# prototype_rev2.net
KiCad netlist of a schematic drawn in EAGLE
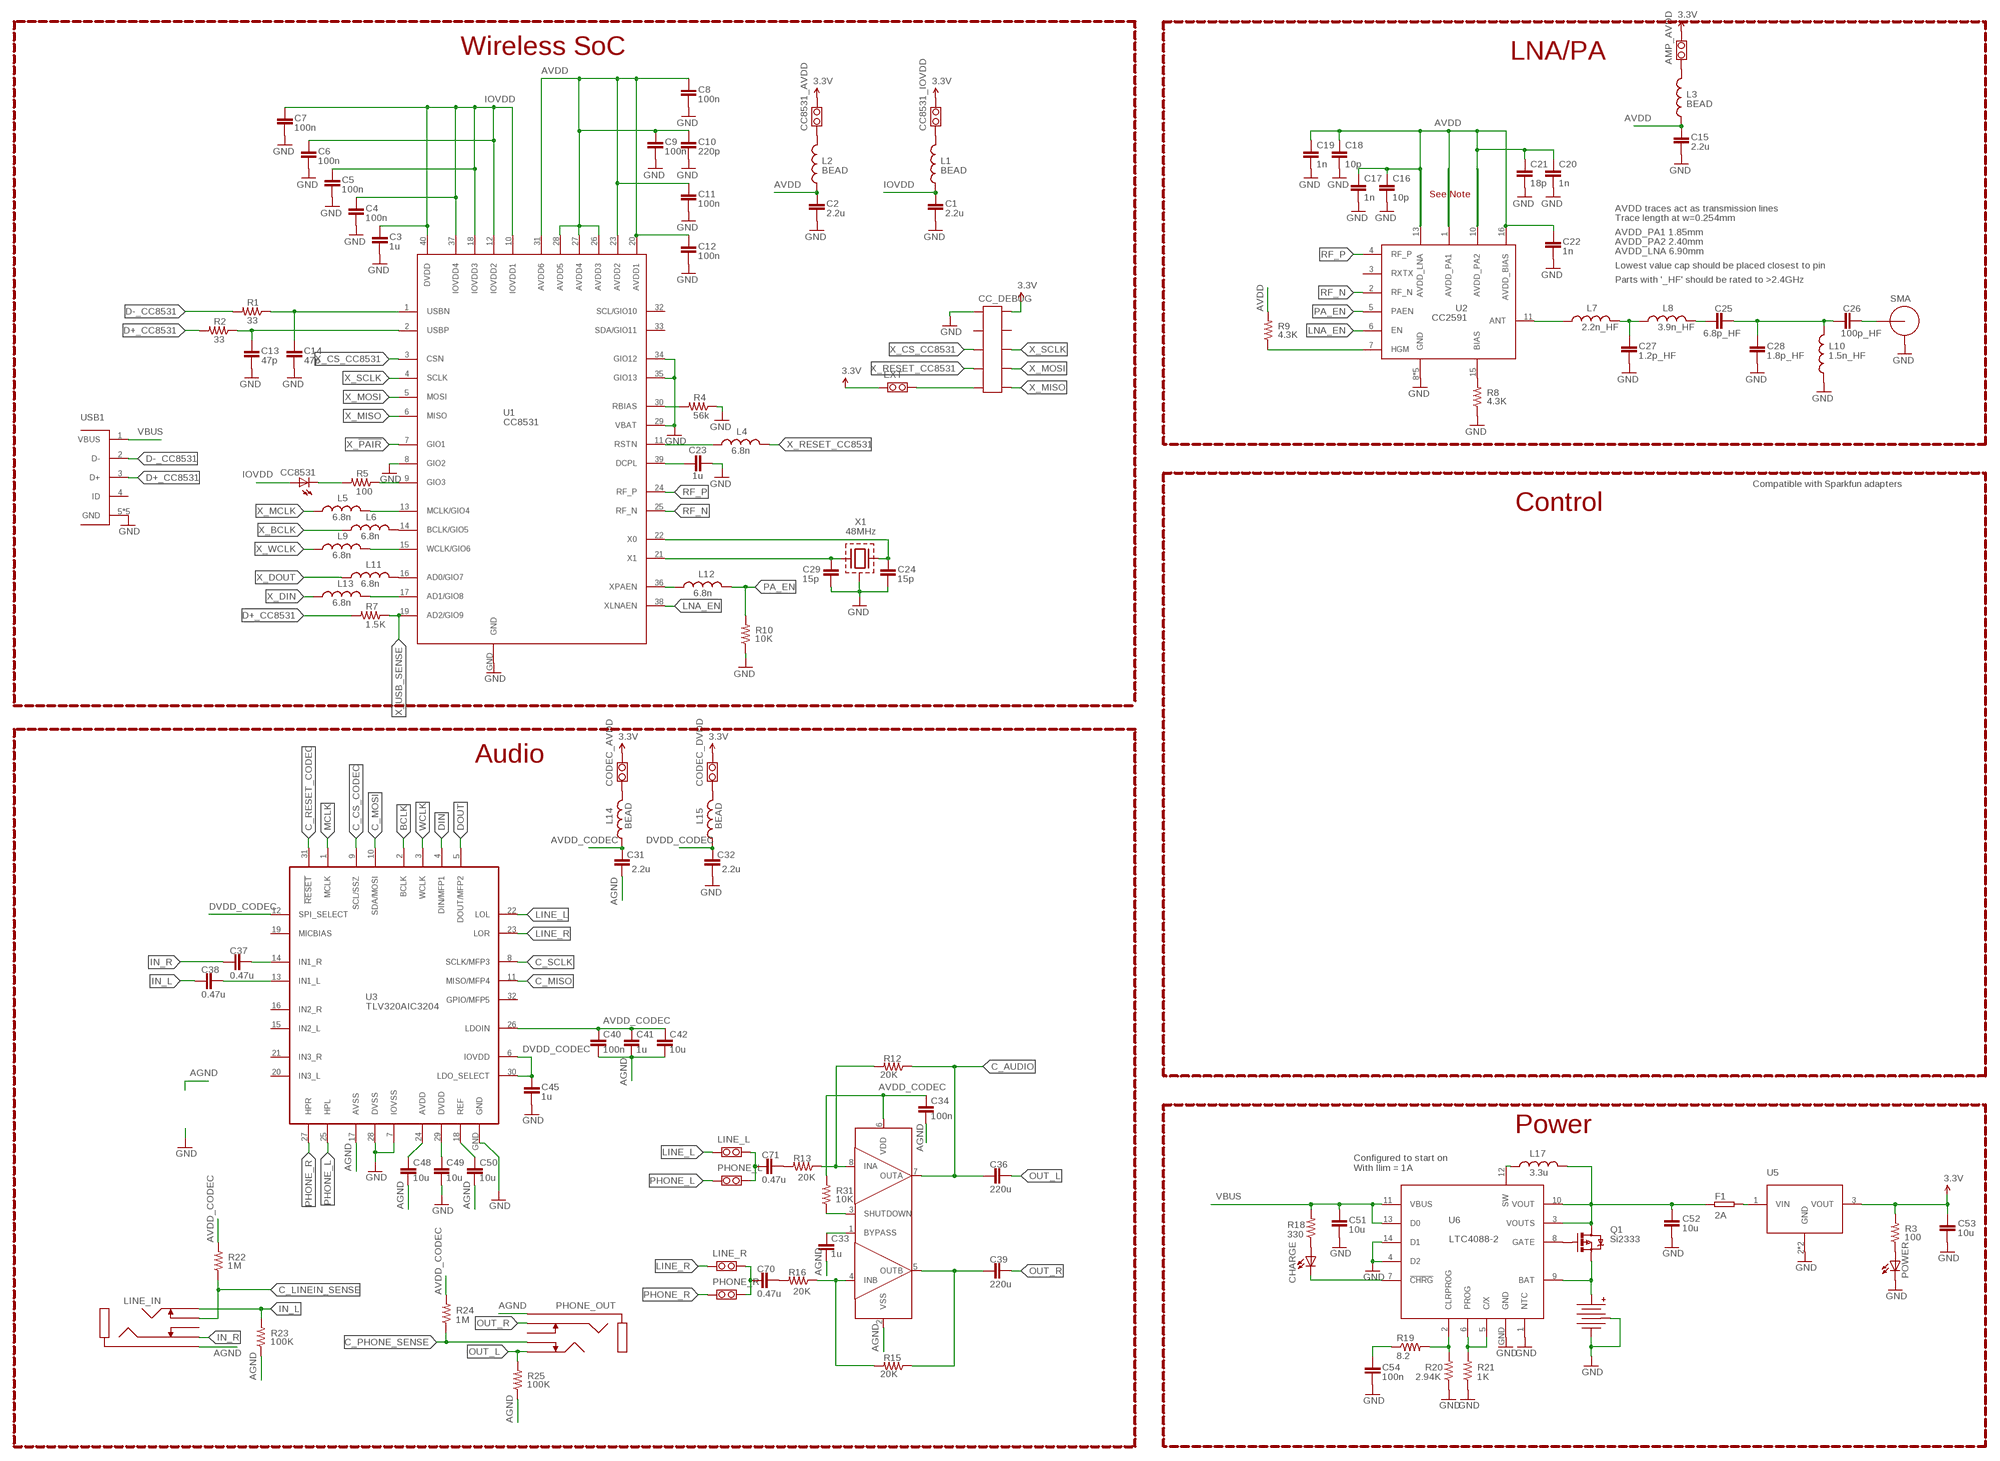
[diagram p0: schematic, sheet 1, part 1 of 3]
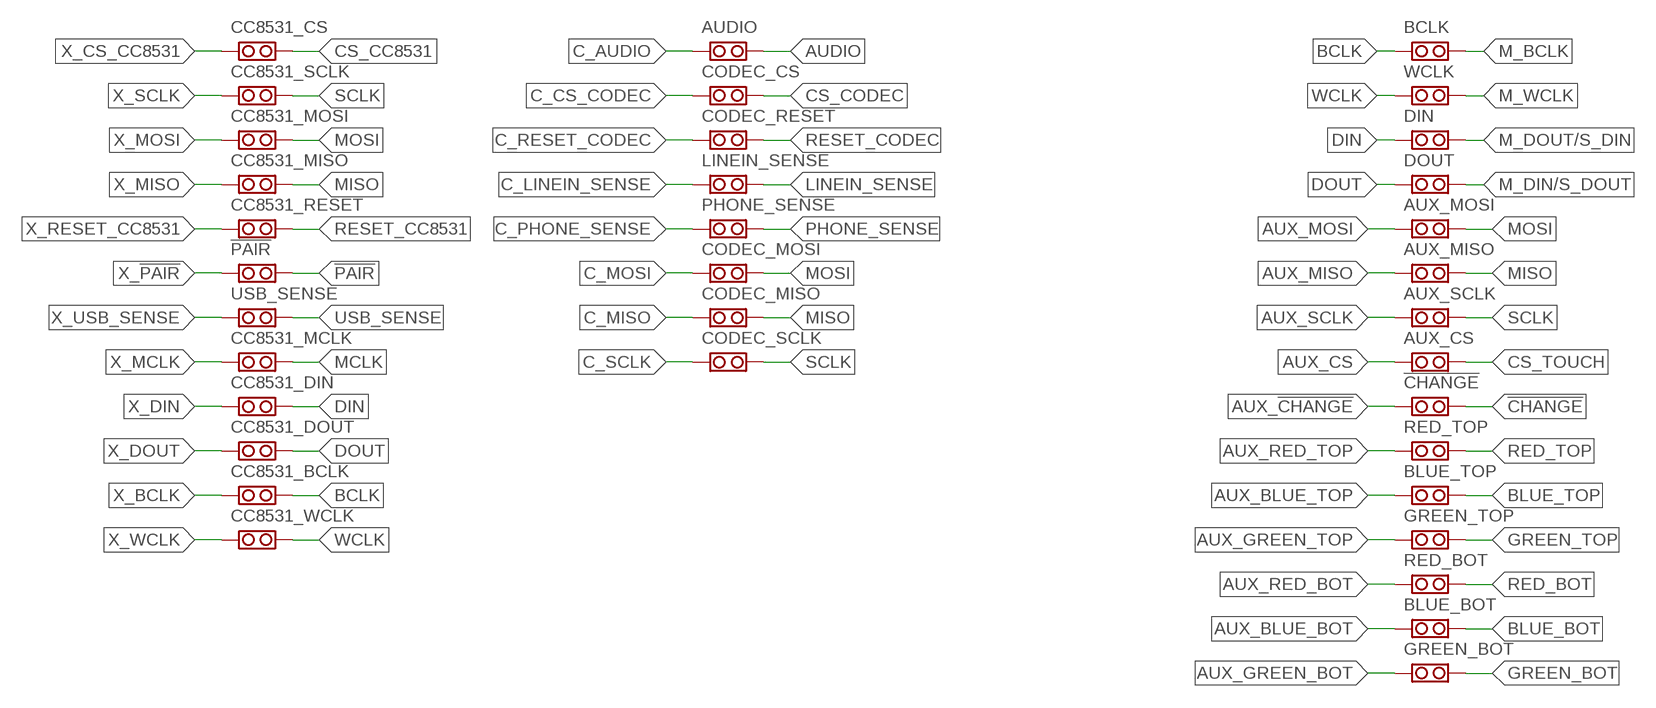
[diagram p1: schematic, sheet 1, part 2 of 3]
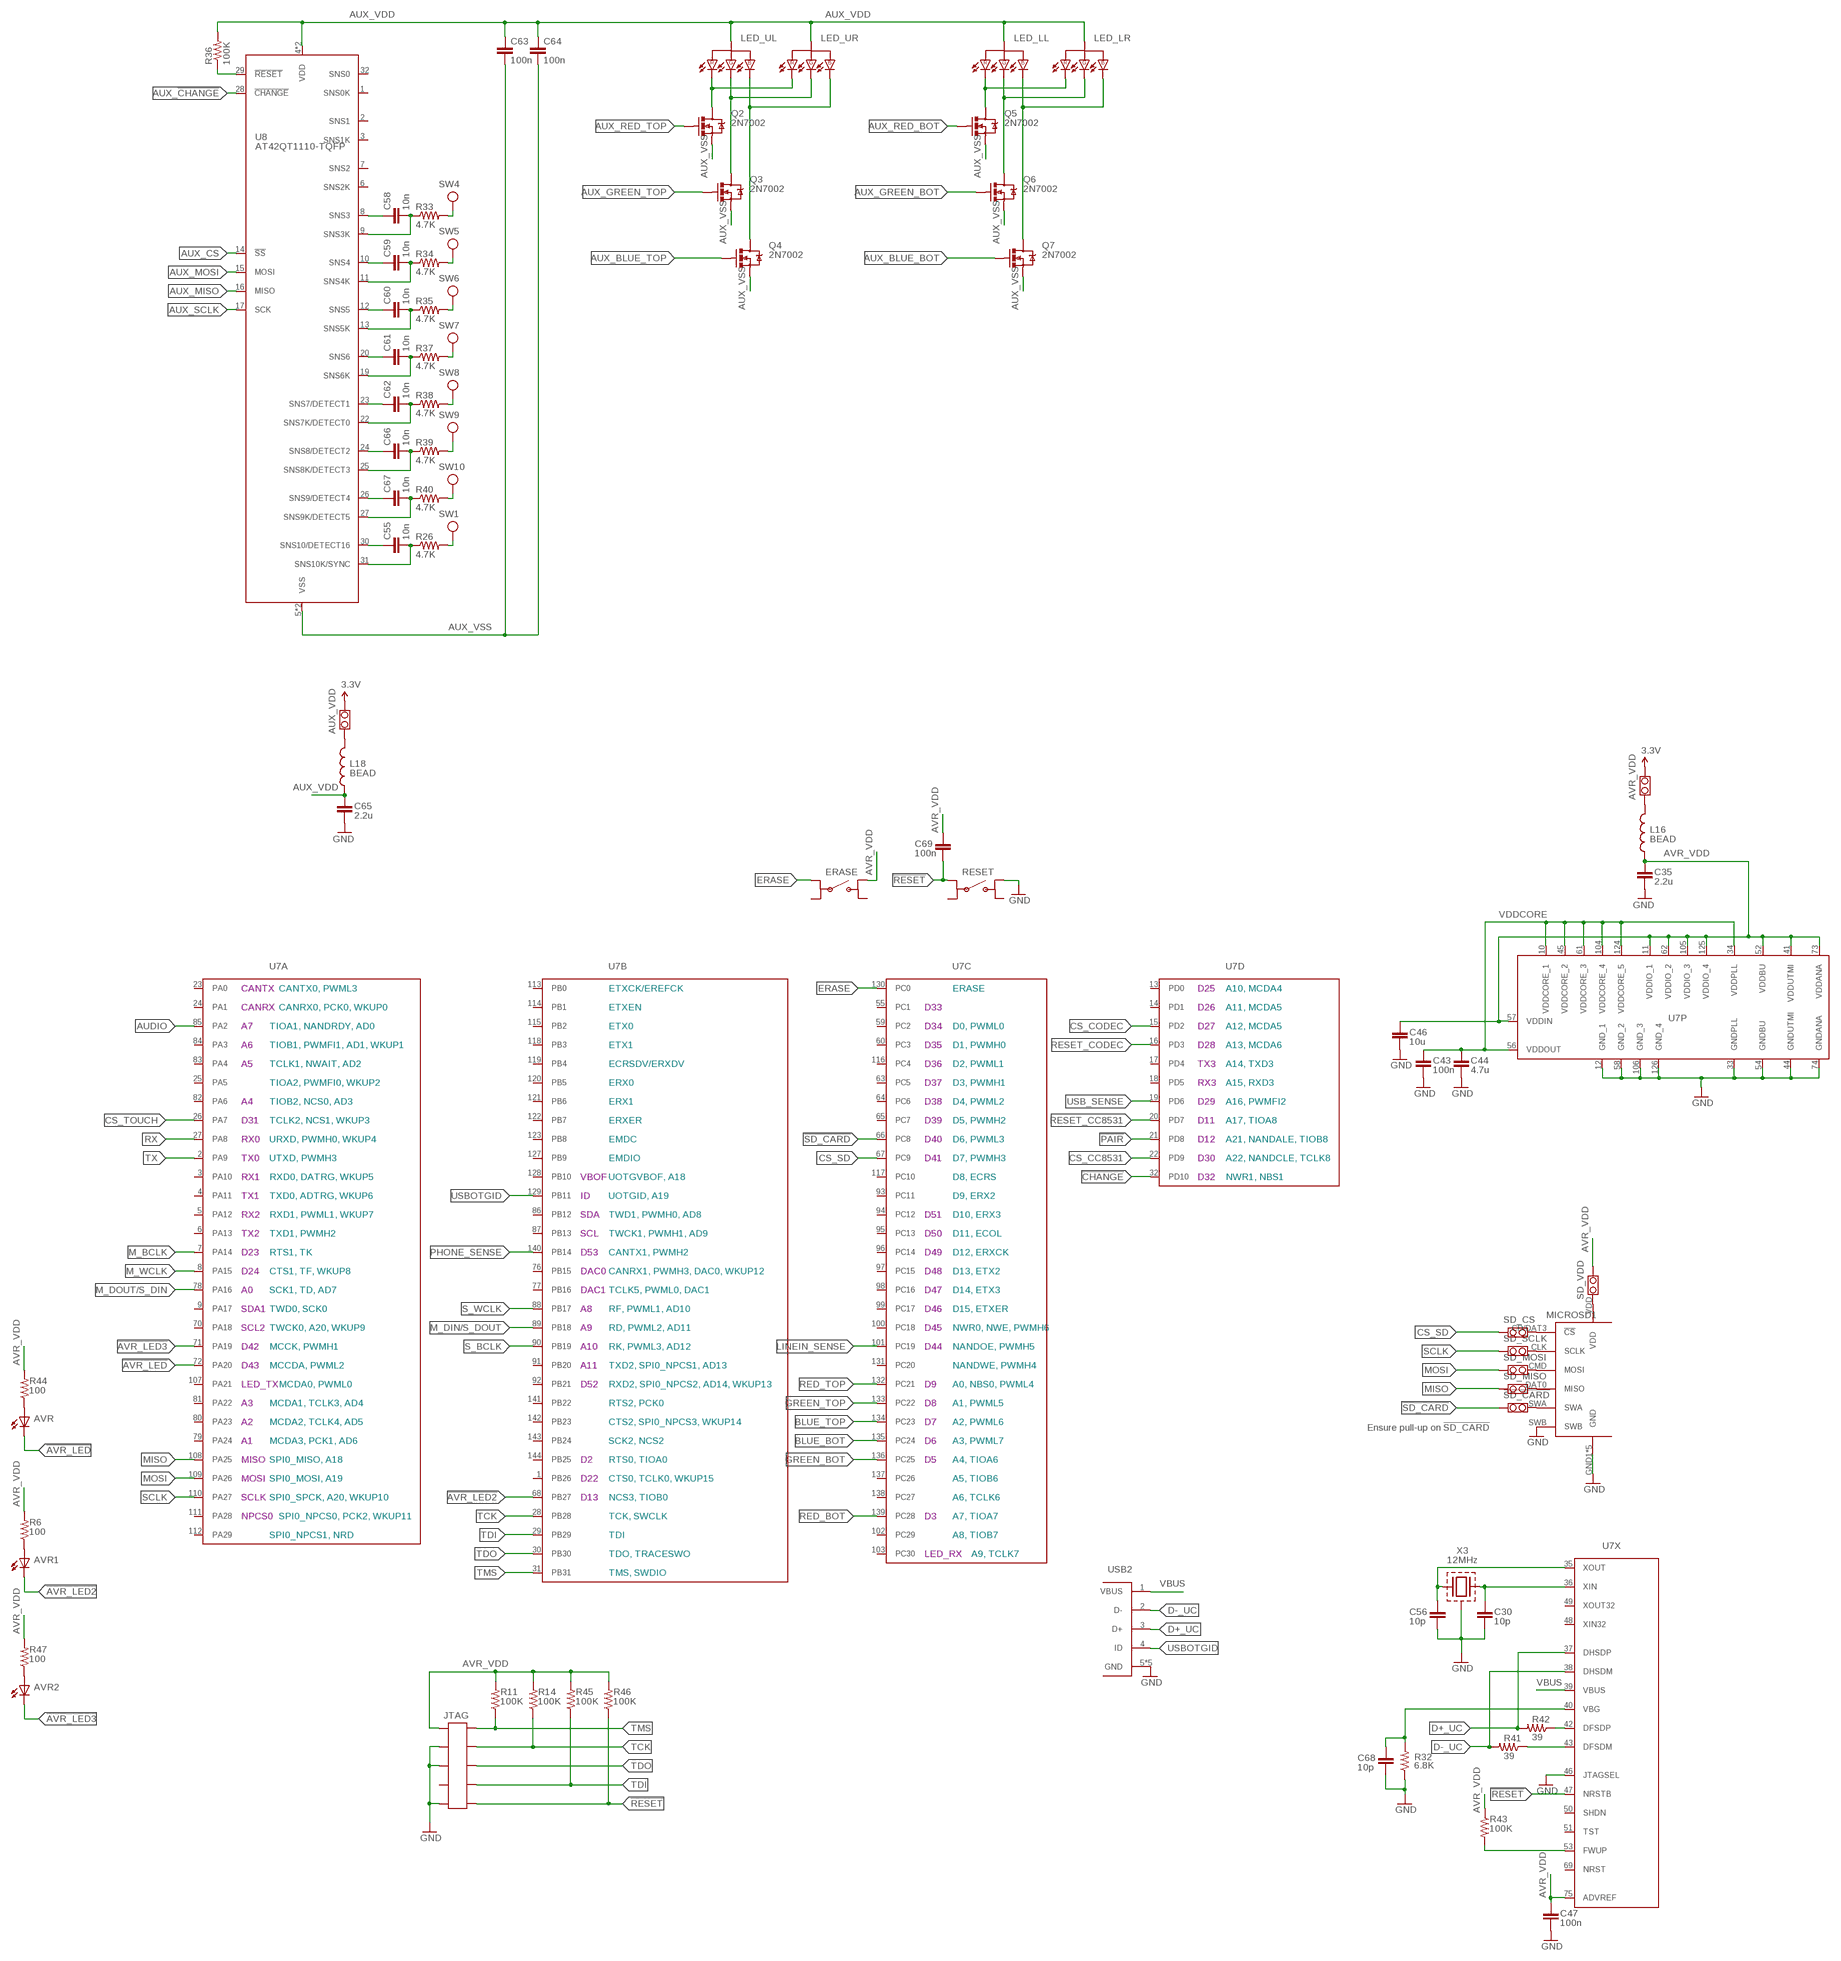
[diagram p2: schematic, sheet 1, part 3 of 3]

(export (version "E")
  (design (tool "Eeschema 10.0.6"))
  (components
    (comp (ref "!CHANGE")
      (value "2P-HEADER-JUMPER")
      (footprint "eagle-import:1X02")
      (libsource (lib "eagle-import") (part "2P-HEADER-JUMPER"))
    )
    (comp (ref "!PAIR")
      (value "2P-HEADER-JUMPER")
      (footprint "eagle-import:1X02")
      (libsource (lib "eagle-import") (part "2P-HEADER-JUMPER"))
    )
    (comp (ref "!SD_CARD")
      (value "2P-HEADER-JUMPER")
      (footprint "eagle-import:1X02")
      (libsource (lib "eagle-import") (part "2P-HEADER-JUMPER"))
    )
    (comp (ref "AMP_AVDD")
      (value "2P-HEADER-JUMPER")
      (footprint "eagle-import:1X02")
      (libsource (lib "eagle-import") (part "2P-HEADER-JUMPER"))
    )
    (comp (ref "AUDIO")
      (value "2P-HEADER-JUMPER")
      (footprint "eagle-import:1X02")
      (libsource (lib "eagle-import") (part "2P-HEADER-JUMPER"))
    )
    (comp (ref "AUX_CS")
      (value "2P-HEADER-JUMPER")
      (footprint "eagle-import:1X02")
      (libsource (lib "eagle-import") (part "2P-HEADER-JUMPER"))
    )
    (comp (ref "AUX_MISO")
      (value "2P-HEADER-JUMPER")
      (footprint "eagle-import:1X02")
      (libsource (lib "eagle-import") (part "2P-HEADER-JUMPER"))
    )
    (comp (ref "AUX_MOSI")
      (value "2P-HEADER-JUMPER")
      (footprint "eagle-import:1X02")
      (libsource (lib "eagle-import") (part "2P-HEADER-JUMPER"))
    )
    (comp (ref "AUX_SCLK")
      (value "2P-HEADER-JUMPER")
      (footprint "eagle-import:1X02")
      (libsource (lib "eagle-import") (part "2P-HEADER-JUMPER"))
    )
    (comp (ref "AUX_VDD")
      (value "2P-HEADER-JUMPER")
      (footprint "eagle-import:1X02")
      (libsource (lib "eagle-import") (part "2P-HEADER-JUMPER"))
    )
    (comp (ref "AVR")
      (value "LED1206")
      (footprint "eagle-import:LED-1206")
      (libsource (lib "eagle-import") (part "LED1206"))
    )
    (comp (ref "AVR1")
      (value "LED1206")
      (footprint "eagle-import:LED-1206")
      (libsource (lib "eagle-import") (part "LED1206"))
    )
    (comp (ref "AVR2")
      (value "LED1206")
      (footprint "eagle-import:LED-1206")
      (libsource (lib "eagle-import") (part "LED1206"))
    )
    (comp (ref "AVR_VDD")
      (value "2P-HEADER-JUMPER")
      (footprint "eagle-import:1X02")
      (libsource (lib "eagle-import") (part "2P-HEADER-JUMPER"))
    )
    (comp (ref "BATTERY")
      (value "BATTERY-LIPO-JST")
      (footprint "eagle-import:1775469-2")
      (libsource (lib "eagle-import") (part "BATTERY-LIPO-JST"))
    )
    (comp (ref "BCLK")
      (value "2P-HEADER-JUMPER")
      (footprint "eagle-import:1X02")
      (libsource (lib "eagle-import") (part "2P-HEADER-JUMPER"))
    )
    (comp (ref "BLUE_BOT")
      (value "2P-HEADER-JUMPER")
      (footprint "eagle-import:1X02")
      (libsource (lib "eagle-import") (part "2P-HEADER-JUMPER"))
    )
    (comp (ref "BLUE_TOP")
      (value "2P-HEADER-JUMPER")
      (footprint "eagle-import:1X02")
      (libsource (lib "eagle-import") (part "2P-HEADER-JUMPER"))
    )
    (comp (ref "C1")
      (value "2.2u")
      (footprint "eagle-import:C0603")
      (libsource (lib "eagle-import") (part "rcl_C-EUC0603"))
    )
    (comp (ref "C2")
      (value "2.2u")
      (footprint "eagle-import:C0603")
      (libsource (lib "eagle-import") (part "rcl_C-EUC0603"))
    )
    (comp (ref "C3")
      (value "1u")
      (footprint "eagle-import:C0603")
      (libsource (lib "eagle-import") (part "rcl_C-EUC0603"))
    )
    (comp (ref "C4")
      (value "100n")
      (footprint "eagle-import:C0603")
      (libsource (lib "eagle-import") (part "rcl_C-EUC0603"))
    )
    (comp (ref "C5")
      (value "100n")
      (footprint "eagle-import:C0603")
      (libsource (lib "eagle-import") (part "rcl_C-EUC0603"))
    )
    (comp (ref "C6")
      (value "100n")
      (footprint "eagle-import:C0603")
      (libsource (lib "eagle-import") (part "rcl_C-EUC0603"))
    )
    (comp (ref "C7")
      (value "100n")
      (footprint "eagle-import:C0603")
      (libsource (lib "eagle-import") (part "rcl_C-EUC0603"))
    )
    (comp (ref "C8")
      (value "100n")
      (footprint "eagle-import:C0603")
      (libsource (lib "eagle-import") (part "rcl_C-EUC0603"))
    )
    (comp (ref "C9")
      (value "100n")
      (footprint "eagle-import:C0603")
      (libsource (lib "eagle-import") (part "rcl_C-EUC0603"))
    )
    (comp (ref "C10")
      (value "220p")
      (footprint "eagle-import:C0603")
      (libsource (lib "eagle-import") (part "rcl_C-EUC0603"))
    )
    (comp (ref "C11")
      (value "100n")
      (footprint "eagle-import:C0603")
      (libsource (lib "eagle-import") (part "rcl_C-EUC0603"))
    )
    (comp (ref "C12")
      (value "100n")
      (footprint "eagle-import:C0603")
      (libsource (lib "eagle-import") (part "rcl_C-EUC0603"))
    )
    (comp (ref "C13")
      (value "47p")
      (footprint "eagle-import:C0603")
      (libsource (lib "eagle-import") (part "rcl_C-EUC0603"))
    )
    (comp (ref "C14")
      (value "47p")
      (footprint "eagle-import:C0603")
      (libsource (lib "eagle-import") (part "rcl_C-EUC0603"))
    )
    (comp (ref "C15")
      (value "2.2u")
      (footprint "eagle-import:C0603")
      (libsource (lib "eagle-import") (part "rcl_C-EUC0603"))
    )
    (comp (ref "C16")
      (value "10p")
      (footprint "eagle-import:C0603")
      (libsource (lib "eagle-import") (part "rcl_C-EUC0603"))
    )
    (comp (ref "C17")
      (value "1n")
      (footprint "eagle-import:C0603")
      (libsource (lib "eagle-import") (part "rcl_C-EUC0603"))
    )
    (comp (ref "C18")
      (value "10p")
      (footprint "eagle-import:C0603")
      (libsource (lib "eagle-import") (part "rcl_C-EUC0603"))
    )
    (comp (ref "C19")
      (value "1n")
      (footprint "eagle-import:C0603")
      (libsource (lib "eagle-import") (part "rcl_C-EUC0603"))
    )
    (comp (ref "C20")
      (value "1n")
      (footprint "eagle-import:C0603")
      (libsource (lib "eagle-import") (part "rcl_C-EUC0603"))
    )
    (comp (ref "C21")
      (value "18p")
      (footprint "eagle-import:C0603")
      (libsource (lib "eagle-import") (part "rcl_C-EUC0603"))
    )
    (comp (ref "C22")
      (value "1n")
      (footprint "eagle-import:C0603")
      (libsource (lib "eagle-import") (part "rcl_C-EUC0603"))
    )
    (comp (ref "C23")
      (value "1u")
      (footprint "eagle-import:C0603")
      (libsource (lib "eagle-import") (part "rcl_C-EUC0603"))
    )
    (comp (ref "C24")
      (value "15p")
      (footprint "eagle-import:C0603")
      (libsource (lib "eagle-import") (part "rcl_C-EUC0603"))
    )
    (comp (ref "C25")
      (value "6.8p_HF")
      (footprint "eagle-import:C0603")
      (libsource (lib "eagle-import") (part "rcl_C-EUC0603"))
    )
    (comp (ref "C26")
      (value "100p_HF")
      (footprint "eagle-import:C0603")
      (libsource (lib "eagle-import") (part "rcl_C-EUC0603"))
    )
    (comp (ref "C27")
      (value "1.2p_HF")
      (footprint "eagle-import:C0603")
      (libsource (lib "eagle-import") (part "rcl_C-EUC0603"))
    )
    (comp (ref "C28")
      (value "1.8p_HF")
      (footprint "eagle-import:C0603")
      (libsource (lib "eagle-import") (part "rcl_C-EUC0603"))
    )
    (comp (ref "C29")
      (value "15p")
      (footprint "eagle-import:C0603")
      (libsource (lib "eagle-import") (part "rcl_C-EUC0603"))
    )
    (comp (ref "C30")
      (value "10p")
      (footprint "eagle-import:C0603")
      (libsource (lib "eagle-import") (part "C-EUC0603"))
    )
    (comp (ref "C31")
      (value "2.2u")
      (footprint "eagle-import:C0603")
      (libsource (lib "eagle-import") (part "rcl_C-EUC0603"))
    )
    (comp (ref "C32")
      (value "2.2u")
      (footprint "eagle-import:C0603")
      (libsource (lib "eagle-import") (part "rcl_C-EUC0603"))
    )
    (comp (ref "C33")
      (value "1u")
      (footprint "eagle-import:C0603")
      (libsource (lib "eagle-import") (part "rcl_C-EUC0603"))
    )
    (comp (ref "C34")
      (value "100n")
      (footprint "eagle-import:C0603")
      (libsource (lib "eagle-import") (part "rcl_C-EUC0603"))
    )
    (comp (ref "C35")
      (value "2.2u")
      (footprint "eagle-import:C0603")
      (libsource (lib "eagle-import") (part "rcl_C-EUC0603"))
    )
    (comp (ref "C36")
      (value "220u")
      (footprint "eagle-import:C1210")
      (libsource (lib "eagle-import") (part "C-EUC1210"))
    )
    (comp (ref "C37")
      (value "0.47u")
      (footprint "eagle-import:C0603")
      (libsource (lib "eagle-import") (part "rcl_C-EUC0603"))
    )
    (comp (ref "C38")
      (value "0.47u")
      (footprint "eagle-import:C0603")
      (libsource (lib "eagle-import") (part "rcl_C-EUC0603"))
    )
    (comp (ref "C39")
      (value "220u")
      (footprint "eagle-import:C1210")
      (libsource (lib "eagle-import") (part "C-EUC1210"))
    )
    (comp (ref "C40")
      (value "100n")
      (footprint "eagle-import:C0603")
      (libsource (lib "eagle-import") (part "rcl_C-EUC0603"))
    )
    (comp (ref "C41")
      (value "1u")
      (footprint "eagle-import:C0603")
      (libsource (lib "eagle-import") (part "rcl_C-EUC0603"))
    )
    (comp (ref "C42")
      (value "10u")
      (footprint "eagle-import:C0603")
      (libsource (lib "eagle-import") (part "rcl_C-EUC0603"))
    )
    (comp (ref "C43")
      (value "100n")
      (footprint "eagle-import:C0603")
      (libsource (lib "eagle-import") (part "rcl_C-EUC0603"))
    )
    (comp (ref "C44")
      (value "4.7u")
      (footprint "eagle-import:C0603")
      (libsource (lib "eagle-import") (part "rcl_C-EUC0603"))
    )
    (comp (ref "C45")
      (value "1u")
      (footprint "eagle-import:C0603")
      (libsource (lib "eagle-import") (part "rcl_C-EUC0603"))
    )
    (comp (ref "C46")
      (value "10u")
      (footprint "eagle-import:C0603")
      (libsource (lib "eagle-import") (part "rcl_C-EUC0603"))
    )
    (comp (ref "C47")
      (value "100n")
      (footprint "eagle-import:C0603")
      (libsource (lib "eagle-import") (part "rcl_C-EUC0603"))
    )
    (comp (ref "C48")
      (value "10u")
      (footprint "eagle-import:C0603")
      (libsource (lib "eagle-import") (part "rcl_C-EUC0603"))
    )
    (comp (ref "C49")
      (value "10u")
      (footprint "eagle-import:C0603")
      (libsource (lib "eagle-import") (part "rcl_C-EUC0603"))
    )
    (comp (ref "C50")
      (value "10u")
      (footprint "eagle-import:C0603")
      (libsource (lib "eagle-import") (part "rcl_C-EUC0603"))
    )
    (comp (ref "C51")
      (value "10u")
      (footprint "eagle-import:C0603")
      (libsource (lib "eagle-import") (part "C-EUC0603"))
    )
    (comp (ref "C52")
      (value "10u")
      (footprint "eagle-import:C0603")
      (libsource (lib "eagle-import") (part "rcl_C-EUC0603"))
    )
    (comp (ref "C53")
      (value "10u")
      (footprint "eagle-import:C0603")
      (libsource (lib "eagle-import") (part "rcl_C-EUC0603"))
    )
    (comp (ref "C54")
      (value "100n")
      (footprint "eagle-import:C0603")
      (libsource (lib "eagle-import") (part "C-EUC0603"))
    )
    (comp (ref "C55")
      (value "10n")
      (footprint "eagle-import:C0603")
      (libsource (lib "eagle-import") (part "rcl_C-EUC0603"))
    )
    (comp (ref "C56")
      (value "10p")
      (footprint "eagle-import:C0603")
      (libsource (lib "eagle-import") (part "C-EUC0603"))
    )
    (comp (ref "C58")
      (value "10n")
      (footprint "eagle-import:C0603")
      (libsource (lib "eagle-import") (part "rcl_C-EUC0603"))
    )
    (comp (ref "C59")
      (value "10n")
      (footprint "eagle-import:C0603")
      (libsource (lib "eagle-import") (part "rcl_C-EUC0603"))
    )
    (comp (ref "C60")
      (value "10n")
      (footprint "eagle-import:C0603")
      (libsource (lib "eagle-import") (part "rcl_C-EUC0603"))
    )
    (comp (ref "C61")
      (value "10n")
      (footprint "eagle-import:C0603")
      (libsource (lib "eagle-import") (part "rcl_C-EUC0603"))
    )
    (comp (ref "C62")
      (value "10n")
      (footprint "eagle-import:C0603")
      (libsource (lib "eagle-import") (part "rcl_C-EUC0603"))
    )
    (comp (ref "C63")
      (value "100n")
      (footprint "eagle-import:C0603")
      (libsource (lib "eagle-import") (part "rcl_C-EUC0603"))
    )
    (comp (ref "C64")
      (value "100n")
      (footprint "eagle-import:C0603")
      (libsource (lib "eagle-import") (part "rcl_C-EUC0603"))
    )
    (comp (ref "C65")
      (value "2.2u")
      (footprint "eagle-import:C0603")
      (libsource (lib "eagle-import") (part "rcl_C-EUC0603"))
    )
    (comp (ref "C66")
      (value "10n")
      (footprint "eagle-import:C0603")
      (libsource (lib "eagle-import") (part "rcl_C-EUC0603"))
    )
    (comp (ref "C67")
      (value "10n")
      (footprint "eagle-import:C0603")
      (libsource (lib "eagle-import") (part "rcl_C-EUC0603"))
    )
    (comp (ref "C68")
      (value "10p")
      (footprint "eagle-import:C0603")
      (libsource (lib "eagle-import") (part "C-EUC0603"))
    )
    (comp (ref "C69")
      (value "100n")
      (footprint "eagle-import:C0603")
      (libsource (lib "eagle-import") (part "C-EUC0603"))
    )
    (comp (ref "C70")
      (value "0.47u")
      (footprint "eagle-import:C0603")
      (libsource (lib "eagle-import") (part "rcl_C-EUC0603"))
    )
    (comp (ref "C71")
      (value "0.47u")
      (footprint "eagle-import:C0603")
      (libsource (lib "eagle-import") (part "rcl_C-EUC0603"))
    )
    (comp (ref "CC8531")
      (value "LED1206")
      (footprint "eagle-import:LED-1206")
      (libsource (lib "eagle-import") (part "LED1206"))
    )
    (comp (ref "CC8531_AVDD")
      (value "2P-HEADER-JUMPER")
      (footprint "eagle-import:1X02")
      (libsource (lib "eagle-import") (part "2P-HEADER-JUMPER"))
    )
    (comp (ref "CC8531_BCLK")
      (value "2P-HEADER-JUMPER")
      (footprint "eagle-import:1X02")
      (libsource (lib "eagle-import") (part "2P-HEADER-JUMPER"))
    )
    (comp (ref "CC8531_CS")
      (value "2P-HEADER-JUMPER")
      (footprint "eagle-import:1X02")
      (libsource (lib "eagle-import") (part "2P-HEADER-JUMPER"))
    )
    (comp (ref "CC8531_DIN")
      (value "2P-HEADER-JUMPER")
      (footprint "eagle-import:1X02")
      (libsource (lib "eagle-import") (part "2P-HEADER-JUMPER"))
    )
    (comp (ref "CC8531_DOUT")
      (value "2P-HEADER-JUMPER")
      (footprint "eagle-import:1X02")
      (libsource (lib "eagle-import") (part "2P-HEADER-JUMPER"))
    )
    (comp (ref "CC8531_IOVDD")
      (value "2P-HEADER-JUMPER")
      (footprint "eagle-import:1X02")
      (libsource (lib "eagle-import") (part "2P-HEADER-JUMPER"))
    )
    (comp (ref "CC8531_MCLK")
      (value "2P-HEADER-JUMPER")
      (footprint "eagle-import:1X02")
      (libsource (lib "eagle-import") (part "2P-HEADER-JUMPER"))
    )
    (comp (ref "CC8531_MISO")
      (value "2P-HEADER-JUMPER")
      (footprint "eagle-import:1X02")
      (libsource (lib "eagle-import") (part "2P-HEADER-JUMPER"))
    )
    (comp (ref "CC8531_MOSI")
      (value "2P-HEADER-JUMPER")
      (footprint "eagle-import:1X02")
      (libsource (lib "eagle-import") (part "2P-HEADER-JUMPER"))
    )
    (comp (ref "CC8531_RESET")
      (value "2P-HEADER-JUMPER")
      (footprint "eagle-import:1X02")
      (libsource (lib "eagle-import") (part "2P-HEADER-JUMPER"))
    )
    (comp (ref "CC8531_SCLK")
      (value "2P-HEADER-JUMPER")
      (footprint "eagle-import:1X02")
      (libsource (lib "eagle-import") (part "2P-HEADER-JUMPER"))
    )
    (comp (ref "CC8531_WCLK")
      (value "2P-HEADER-JUMPER")
      (footprint "eagle-import:1X02")
      (libsource (lib "eagle-import") (part "2P-HEADER-JUMPER"))
    )
    (comp (ref "CC_DEBUG")
      (value "HEADER-10P-SMD-MALE2")
      (footprint "eagle-import:HEADER-10P-1.27MM")
      (libsource (lib "eagle-import") (part "HEADER-10P-SMD-MALE2"))
    )
    (comp (ref "CHARGE")
      (value "LED1206")
      (footprint "eagle-import:LED-1206")
      (libsource (lib "eagle-import") (part "LED1206"))
    )
    (comp (ref "CODEC_AVDD")
      (value "2P-HEADER-JUMPER")
      (footprint "eagle-import:1X02")
      (libsource (lib "eagle-import") (part "2P-HEADER-JUMPER"))
    )
    (comp (ref "CODEC_CS")
      (value "2P-HEADER-JUMPER")
      (footprint "eagle-import:1X02")
      (libsource (lib "eagle-import") (part "2P-HEADER-JUMPER"))
    )
    (comp (ref "CODEC_DVDD")
      (value "2P-HEADER-JUMPER")
      (footprint "eagle-import:1X02")
      (libsource (lib "eagle-import") (part "2P-HEADER-JUMPER"))
    )
    (comp (ref "CODEC_MISO")
      (value "2P-HEADER-JUMPER")
      (footprint "eagle-import:1X02")
      (libsource (lib "eagle-import") (part "2P-HEADER-JUMPER"))
    )
    (comp (ref "CODEC_MOSI")
      (value "2P-HEADER-JUMPER")
      (footprint "eagle-import:1X02")
      (libsource (lib "eagle-import") (part "2P-HEADER-JUMPER"))
    )
    (comp (ref "CODEC_RESET")
      (value "2P-HEADER-JUMPER")
      (footprint "eagle-import:1X02")
      (libsource (lib "eagle-import") (part "2P-HEADER-JUMPER"))
    )
    (comp (ref "CODEC_SCLK")
      (value "2P-HEADER-JUMPER")
      (footprint "eagle-import:1X02")
      (libsource (lib "eagle-import") (part "2P-HEADER-JUMPER"))
    )
    (comp (ref "DIN")
      (value "2P-HEADER-JUMPER")
      (footprint "eagle-import:1X02")
      (libsource (lib "eagle-import") (part "2P-HEADER-JUMPER"))
    )
    (comp (ref "DOUT")
      (value "2P-HEADER-JUMPER")
      (footprint "eagle-import:1X02")
      (libsource (lib "eagle-import") (part "2P-HEADER-JUMPER"))
    )
    (comp (ref "ERASE")
      (value "TACT_SWITCH-PTS-525")
      (footprint "eagle-import:PTS-525")
      (libsource (lib "eagle-import") (part "TACT_SWITCH-PTS-525"))
    )
    (comp (ref "EXT")
      (value "2P-HEADER-JUMPER")
      (footprint "eagle-import:1X02")
      (libsource (lib "eagle-import") (part "2P-HEADER-JUMPER"))
    )
    (comp (ref "F1")
      (value "2A")
      (footprint "eagle-import:1210")
      (libsource (lib "eagle-import") (part "PTC_FUSE"))
    )
    (comp (ref "GREEN_BOT")
      (value "2P-HEADER-JUMPER")
      (footprint "eagle-import:1X02")
      (libsource (lib "eagle-import") (part "2P-HEADER-JUMPER"))
    )
    (comp (ref "GREEN_TOP")
      (value "2P-HEADER-JUMPER")
      (footprint "eagle-import:1X02")
      (libsource (lib "eagle-import") (part "2P-HEADER-JUMPER"))
    )
    (comp (ref "JTAG")
      (value "HEADER-10P-SMD-MALE2")
      (footprint "eagle-import:HEADER-10P-1.27MM")
      (libsource (lib "eagle-import") (part "HEADER-10P-SMD-MALE2"))
    )
    (comp (ref "L1")
      (value "BEAD")
      (footprint "eagle-import:0603")
      (libsource (lib "eagle-import") (part "INDUCTOR0603"))
    )
    (comp (ref "L2")
      (value "BEAD")
      (footprint "eagle-import:0603")
      (libsource (lib "eagle-import") (part "INDUCTOR0603"))
    )
    (comp (ref "L3")
      (value "BEAD")
      (footprint "eagle-import:0603")
      (libsource (lib "eagle-import") (part "INDUCTOR0603"))
    )
    (comp (ref "L4")
      (value "6.8n")
      (footprint "eagle-import:0603")
      (libsource (lib "eagle-import") (part "INDUCTOR0603"))
    )
    (comp (ref "L5")
      (value "6.8n")
      (footprint "eagle-import:0603")
      (libsource (lib "eagle-import") (part "INDUCTOR0603"))
    )
    (comp (ref "L6")
      (value "6.8n")
      (footprint "eagle-import:0603")
      (libsource (lib "eagle-import") (part "INDUCTOR0603"))
    )
    (comp (ref "L7")
      (value "2.2n_HF")
      (footprint "eagle-import:0603")
      (libsource (lib "eagle-import") (part "INDUCTOR0603"))
    )
    (comp (ref "L8")
      (value "3.9n_HF")
      (footprint "eagle-import:0603")
      (libsource (lib "eagle-import") (part "INDUCTOR0603"))
    )
    (comp (ref "L9")
      (value "6.8n")
      (footprint "eagle-import:0603")
      (libsource (lib "eagle-import") (part "INDUCTOR0603"))
    )
    (comp (ref "L10")
      (value "1.5n_HF")
      (footprint "eagle-import:0603")
      (libsource (lib "eagle-import") (part "INDUCTOR0603"))
    )
    (comp (ref "L11")
      (value "6.8n")
      (footprint "eagle-import:0603")
      (libsource (lib "eagle-import") (part "INDUCTOR0603"))
    )
    (comp (ref "L12")
      (value "6.8n")
      (footprint "eagle-import:0603")
      (libsource (lib "eagle-import") (part "INDUCTOR0603"))
    )
    (comp (ref "L13")
      (value "6.8n")
      (footprint "eagle-import:0603")
      (libsource (lib "eagle-import") (part "INDUCTOR0603"))
    )
    (comp (ref "L14")
      (value "BEAD")
      (footprint "eagle-import:0603")
      (libsource (lib "eagle-import") (part "INDUCTOR0603"))
    )
    (comp (ref "L15")
      (value "BEAD")
      (footprint "eagle-import:0603")
      (libsource (lib "eagle-import") (part "INDUCTOR0603"))
    )
    (comp (ref "L16")
      (value "BEAD")
      (footprint "eagle-import:0603")
      (libsource (lib "eagle-import") (part "INDUCTOR0603"))
    )
    (comp (ref "L17")
      (value "3.3u")
      (footprint "eagle-import:IFSC-1111AB-01")
      (libsource (lib "eagle-import") (part "IFSC-1111AB-01"))
    )
    (comp (ref "L18")
      (value "BEAD")
      (footprint "eagle-import:0603")
      (libsource (lib "eagle-import") (part "INDUCTOR0603"))
    )
    (comp (ref "LED_LL")
      (value "LED_RGB")
      (footprint "eagle-import:PLCC-4")
      (libsource (lib "eagle-import") (part "LED_RGB"))
    )
    (comp (ref "LED_LR")
      (value "LED_RGB")
      (footprint "eagle-import:PLCC-4")
      (libsource (lib "eagle-import") (part "LED_RGB"))
    )
    (comp (ref "LED_UL")
      (value "LED_RGB")
      (footprint "eagle-import:PLCC-4")
      (libsource (lib "eagle-import") (part "LED_RGB"))
    )
    (comp (ref "LED_UR")
      (value "LED_RGB")
      (footprint "eagle-import:PLCC-4")
      (libsource (lib "eagle-import") (part "LED_RGB"))
    )
    (comp (ref "LINEIN_SENSE")
      (value "2P-HEADER-JUMPER")
      (footprint "eagle-import:1X02")
      (libsource (lib "eagle-import") (part "2P-HEADER-JUMPER"))
    )
    (comp (ref "LINE_IN")
      (value "PHONE_SW-STX-35332-5N")
      (footprint "eagle-import:STX-35332-5N")
      (libsource (lib "eagle-import") (part "PHONE_SW-STX-35332-5N"))
    )
    (comp (ref "LINE_L")
      (value "2P-HEADER-JUMPER")
      (footprint "eagle-import:1X02")
      (libsource (lib "eagle-import") (part "2P-HEADER-JUMPER"))
    )
    (comp (ref "LINE_R")
      (value "2P-HEADER-JUMPER")
      (footprint "eagle-import:1X02")
      (libsource (lib "eagle-import") (part "2P-HEADER-JUMPER"))
    )
    (comp (ref "MICROSD1")
      (value "MICROSD104031-0811")
      (footprint "eagle-import:MOLEX_104031-0811")
      (libsource (lib "eagle-import") (part "MICROSD104031-0811"))
    )
    (comp (ref "PHONE_L")
      (value "2P-HEADER-JUMPER")
      (footprint "eagle-import:1X02")
      (libsource (lib "eagle-import") (part "2P-HEADER-JUMPER"))
    )
    (comp (ref "PHONE_OUT")
      (value "PHONE_SW-STX-35332-5N")
      (footprint "eagle-import:STX-35332-5N")
      (libsource (lib "eagle-import") (part "PHONE_SW-STX-35332-5N"))
    )
    (comp (ref "PHONE_R")
      (value "2P-HEADER-JUMPER")
      (footprint "eagle-import:1X02")
      (libsource (lib "eagle-import") (part "2P-HEADER-JUMPER"))
    )
    (comp (ref "PHONE_SENSE")
      (value "2P-HEADER-JUMPER")
      (footprint "eagle-import:1X02")
      (libsource (lib "eagle-import") (part "2P-HEADER-JUMPER"))
    )
    (comp (ref "POWER")
      (value "LED1206")
      (footprint "eagle-import:LED-1206")
      (libsource (lib "eagle-import") (part "LED1206"))
    )
    (comp (ref "Q1")
      (value "Si2333")
      (footprint "eagle-import:SOT23-3")
      (libsource (lib "eagle-import") (part "MOSFET-PCHANNELSMD"))
    )
    (comp (ref "Q2")
      (value "2N7002")
      (footprint "eagle-import:SOT23-3")
      (libsource (lib "eagle-import") (part "MOSFET-NCHANNELSMD"))
    )
    (comp (ref "Q3")
      (value "2N7002")
      (footprint "eagle-import:SOT23-3")
      (libsource (lib "eagle-import") (part "MOSFET-NCHANNELSMD"))
    )
    (comp (ref "Q4")
      (value "2N7002")
      (footprint "eagle-import:SOT23-3")
      (libsource (lib "eagle-import") (part "MOSFET-NCHANNELSMD"))
    )
    (comp (ref "Q5")
      (value "2N7002")
      (footprint "eagle-import:SOT23-3")
      (libsource (lib "eagle-import") (part "MOSFET-NCHANNELSMD"))
    )
    (comp (ref "Q6")
      (value "2N7002")
      (footprint "eagle-import:SOT23-3")
      (libsource (lib "eagle-import") (part "MOSFET-NCHANNELSMD"))
    )
    (comp (ref "Q7")
      (value "2N7002")
      (footprint "eagle-import:SOT23-3")
      (libsource (lib "eagle-import") (part "MOSFET-NCHANNELSMD"))
    )
    (comp (ref "R1")
      (value "33")
      (footprint "eagle-import:R0603")
      (libsource (lib "eagle-import") (part "rcl_R-US_R0603"))
    )
    (comp (ref "R2")
      (value "33")
      (footprint "eagle-import:R0603")
      (libsource (lib "eagle-import") (part "rcl_R-US_R0603"))
    )
    (comp (ref "R3")
      (value "100")
      (footprint "eagle-import:R0603")
      (libsource (lib "eagle-import") (part "rcl_R-US_R0603"))
    )
    (comp (ref "R4")
      (value "56k")
      (footprint "eagle-import:R0603")
      (libsource (lib "eagle-import") (part "rcl_R-US_R0603"))
    )
    (comp (ref "R5")
      (value "100")
      (footprint "eagle-import:R0603")
      (libsource (lib "eagle-import") (part "rcl_R-US_R0603"))
    )
    (comp (ref "R6")
      (value "100")
      (footprint "eagle-import:R0603")
      (libsource (lib "eagle-import") (part "rcl_R-US_R0603"))
    )
    (comp (ref "R7")
      (value "1.5K")
      (footprint "eagle-import:R0603")
      (libsource (lib "eagle-import") (part "rcl_R-US_R0603"))
    )
    (comp (ref "R8")
      (value "4.3K")
      (footprint "eagle-import:R0603")
      (libsource (lib "eagle-import") (part "rcl_R-US_R0603"))
    )
    (comp (ref "R9")
      (value "4.3K")
      (footprint "eagle-import:R0603")
      (libsource (lib "eagle-import") (part "rcl_R-US_R0603"))
    )
    (comp (ref "R10")
      (value "10K")
      (footprint "eagle-import:R0603")
      (libsource (lib "eagle-import") (part "rcl_R-US_R0603"))
    )
    (comp (ref "R11")
      (value "100K")
      (footprint "eagle-import:R0603")
      (libsource (lib "eagle-import") (part "rcl_R-US_R0603"))
    )
    (comp (ref "R12")
      (value "20K")
      (footprint "eagle-import:R0603")
      (libsource (lib "eagle-import") (part "R-US_R0603"))
    )
    (comp (ref "R13")
      (value "20K")
      (footprint "eagle-import:R0603")
      (libsource (lib "eagle-import") (part "R-US_R0603"))
    )
    (comp (ref "R14")
      (value "100K")
      (footprint "eagle-import:R0603")
      (libsource (lib "eagle-import") (part "rcl_R-US_R0603"))
    )
    (comp (ref "R15")
      (value "20K")
      (footprint "eagle-import:R0603")
      (libsource (lib "eagle-import") (part "R-US_R0603"))
    )
    (comp (ref "R16")
      (value "20K")
      (footprint "eagle-import:R0603")
      (libsource (lib "eagle-import") (part "R-US_R0603"))
    )
    (comp (ref "R18")
      (value "330")
      (footprint "eagle-import:R0603")
      (libsource (lib "eagle-import") (part "R-US_R0603"))
    )
    (comp (ref "R19")
      (value "8.2")
      (footprint "eagle-import:R0603")
      (libsource (lib "eagle-import") (part "R-US_R0603"))
    )
    (comp (ref "R20")
      (value "2.94K")
      (footprint "eagle-import:R0603")
      (libsource (lib "eagle-import") (part "R-US_R0603"))
    )
    (comp (ref "R21")
      (value "1K")
      (footprint "eagle-import:R0603")
      (libsource (lib "eagle-import") (part "R-US_R0603"))
    )
    (comp (ref "R22")
      (value "1M")
      (footprint "eagle-import:R0603")
      (libsource (lib "eagle-import") (part "rcl_R-US_R0603"))
    )
    (comp (ref "R23")
      (value "100K")
      (footprint "eagle-import:R0603")
      (libsource (lib "eagle-import") (part "rcl_R-US_R0603"))
    )
    (comp (ref "R24")
      (value "1M")
      (footprint "eagle-import:R0603")
      (libsource (lib "eagle-import") (part "rcl_R-US_R0603"))
    )
    (comp (ref "R25")
      (value "100K")
      (footprint "eagle-import:R0603")
      (libsource (lib "eagle-import") (part "rcl_R-US_R0603"))
    )
    (comp (ref "R26")
      (value "4.7K")
      (footprint "eagle-import:R0603")
      (libsource (lib "eagle-import") (part "rcl_R-US_R0603"))
    )
    (comp (ref "R31")
      (value "10K")
      (footprint "eagle-import:R0603")
      (libsource (lib "eagle-import") (part "rcl_R-US_R0603"))
    )
    (comp (ref "R32")
      (value "6.8K")
      (footprint "eagle-import:R0603")
      (libsource (lib "eagle-import") (part "rcl_R-US_R0603"))
    )
    (comp (ref "R33")
      (value "4.7K")
      (footprint "eagle-import:R0603")
      (libsource (lib "eagle-import") (part "rcl_R-US_R0603"))
    )
    (comp (ref "R34")
      (value "4.7K")
      (footprint "eagle-import:R0603")
      (libsource (lib "eagle-import") (part "rcl_R-US_R0603"))
    )
    (comp (ref "R35")
      (value "4.7K")
      (footprint "eagle-import:R0603")
      (libsource (lib "eagle-import") (part "rcl_R-US_R0603"))
    )
    (comp (ref "R36")
      (value "100K")
      (footprint "eagle-import:R0603")
      (libsource (lib "eagle-import") (part "rcl_R-US_R0603"))
    )
    (comp (ref "R37")
      (value "4.7K")
      (footprint "eagle-import:R0603")
      (libsource (lib "eagle-import") (part "rcl_R-US_R0603"))
    )
    (comp (ref "R38")
      (value "4.7K")
      (footprint "eagle-import:R0603")
      (libsource (lib "eagle-import") (part "rcl_R-US_R0603"))
    )
    (comp (ref "R39")
      (value "4.7K")
      (footprint "eagle-import:R0603")
      (libsource (lib "eagle-import") (part "rcl_R-US_R0603"))
    )
    (comp (ref "R40")
      (value "4.7K")
      (footprint "eagle-import:R0603")
      (libsource (lib "eagle-import") (part "rcl_R-US_R0603"))
    )
    (comp (ref "R41")
      (value "39")
      (footprint "eagle-import:R0603")
      (libsource (lib "eagle-import") (part "rcl_R-US_R0603"))
    )
    (comp (ref "R42")
      (value "39")
      (footprint "eagle-import:R0603")
      (libsource (lib "eagle-import") (part "rcl_R-US_R0603"))
    )
    (comp (ref "R43")
      (value "100K")
      (footprint "eagle-import:R0603")
      (libsource (lib "eagle-import") (part "rcl_R-US_R0603"))
    )
    (comp (ref "R44")
      (value "100")
      (footprint "eagle-import:R0603")
      (libsource (lib "eagle-import") (part "rcl_R-US_R0603"))
    )
    (comp (ref "R45")
      (value "100K")
      (footprint "eagle-import:R0603")
      (libsource (lib "eagle-import") (part "rcl_R-US_R0603"))
    )
    (comp (ref "R46")
      (value "100K")
      (footprint "eagle-import:R0603")
      (libsource (lib "eagle-import") (part "rcl_R-US_R0603"))
    )
    (comp (ref "R47")
      (value "100")
      (footprint "eagle-import:R0603")
      (libsource (lib "eagle-import") (part "rcl_R-US_R0603"))
    )
    (comp (ref "RED_BOT")
      (value "2P-HEADER-JUMPER")
      (footprint "eagle-import:1X02")
      (libsource (lib "eagle-import") (part "2P-HEADER-JUMPER"))
    )
    (comp (ref "RED_TOP")
      (value "2P-HEADER-JUMPER")
      (footprint "eagle-import:1X02")
      (libsource (lib "eagle-import") (part "2P-HEADER-JUMPER"))
    )
    (comp (ref "RESET")
      (value "TACT_SWITCH-PTS-525")
      (footprint "eagle-import:PTS-525")
      (libsource (lib "eagle-import") (part "TACT_SWITCH-PTS-525"))
    )
    (comp (ref "SD_CS")
      (value "2P-HEADER-JUMPER")
      (footprint "eagle-import:1X02")
      (libsource (lib "eagle-import") (part "2P-HEADER-JUMPER"))
    )
    (comp (ref "SD_MISO")
      (value "2P-HEADER-JUMPER")
      (footprint "eagle-import:1X02")
      (libsource (lib "eagle-import") (part "2P-HEADER-JUMPER"))
    )
    (comp (ref "SD_MOSI")
      (value "2P-HEADER-JUMPER")
      (footprint "eagle-import:1X02")
      (libsource (lib "eagle-import") (part "2P-HEADER-JUMPER"))
    )
    (comp (ref "SD_SCLK")
      (value "2P-HEADER-JUMPER")
      (footprint "eagle-import:1X02")
      (libsource (lib "eagle-import") (part "2P-HEADER-JUMPER"))
    )
    (comp (ref "SD_VDD")
      (value "2P-HEADER-JUMPER")
      (footprint "eagle-import:1X02")
      (libsource (lib "eagle-import") (part "2P-HEADER-JUMPER"))
    )
    (comp (ref "SMA")
      (value "SMA-REVSMA-0.62")
      (footprint "eagle-import:CONREVSMA003.062")
      (libsource (lib "eagle-import") (part "SMA-REVSMA-0.62"))
    )
    (comp (ref "SW1")
      (value "TOUCH_PAD-CIRCLE-15MM")
      (footprint "eagle-import:TOUCH-CIRCLE-15MM")
      (libsource (lib "eagle-import") (part "TOUCH_PAD-CIRCLE-15MM"))
    )
    (comp (ref "SW4")
      (value "TOUCH_PAD-CIRCLE-15MM")
      (footprint "eagle-import:TOUCH-CIRCLE-15MM")
      (libsource (lib "eagle-import") (part "TOUCH_PAD-CIRCLE-15MM"))
    )
    (comp (ref "SW5")
      (value "TOUCH_PAD-CIRCLE-15MM")
      (footprint "eagle-import:TOUCH-CIRCLE-15MM")
      (libsource (lib "eagle-import") (part "TOUCH_PAD-CIRCLE-15MM"))
    )
    (comp (ref "SW6")
      (value "TOUCH_PAD-CIRCLE-15MM")
      (footprint "eagle-import:TOUCH-CIRCLE-15MM")
      (libsource (lib "eagle-import") (part "TOUCH_PAD-CIRCLE-15MM"))
    )
    (comp (ref "SW7")
      (value "TOUCH_PAD-CIRCLE-15MM")
      (footprint "eagle-import:TOUCH-CIRCLE-15MM")
      (libsource (lib "eagle-import") (part "TOUCH_PAD-CIRCLE-15MM"))
    )
    (comp (ref "SW8")
      (value "TOUCH_PAD-CIRCLE-15MM")
      (footprint "eagle-import:TOUCH-CIRCLE-15MM")
      (libsource (lib "eagle-import") (part "TOUCH_PAD-CIRCLE-15MM"))
    )
    (comp (ref "SW9")
      (value "TOUCH_PAD-CIRCLE-15MM")
      (footprint "eagle-import:TOUCH-CIRCLE-15MM")
      (libsource (lib "eagle-import") (part "TOUCH_PAD-CIRCLE-15MM"))
    )
    (comp (ref "SW10")
      (value "TOUCH_PAD-CIRCLE-15MM")
      (footprint "eagle-import:TOUCH-CIRCLE-15MM")
      (libsource (lib "eagle-import") (part "TOUCH_PAD-CIRCLE-15MM"))
    )
    (comp (ref "U1")
      (value "CC8531")
      (footprint "eagle-import:S-PVQFN-N40")
      (libsource (lib "eagle-import") (part "CC8531"))
    )
    (comp (ref "U2")
      (value "CC2591")
      (footprint "eagle-import:S-PVQFN-N16")
      (libsource (lib "eagle-import") (part "CC2591"))
    )
    (comp (ref "U3")
      (value "TLV320AIC3204")
      (footprint "eagle-import:S-PVQFN-N32")
      (libsource (lib "eagle-import") (part "TLV320AIC3204"))
    )
    (comp (ref "U5")
      (value "MCP1826-SOT223")
      (footprint "eagle-import:SOT-223")
      (libsource (lib "eagle-import") (part "MCP1826-SOT223"))
    )
    (comp (ref "U6")
      (value "LTC4088-2")
      (footprint "eagle-import:DFN-14")
      (libsource (lib "eagle-import") (part "LTC4088-1/2"))
    )
    (comp (ref "U7")
      (value "ATSAM3X8E_ALT-LQFP-144")
      (footprint "eagle-import:LQFP-144")
      (libsource (lib "eagle-import") (part "ATSAM3X8E_ALT-LQFP-144"))
    )
    (comp (ref "U8")
      (value "AT42QT1110-TQFP")
      (footprint "eagle-import:S-PQFP-N32")
      (libsource (lib "eagle-import") (part "AT42QT1110-TQFP"))
    )
    (comp (ref "U9")
      (value "LM4881")
      (footprint "eagle-import:SO08")
      (libsource (lib "eagle-import") (part "LM4881"))
    )
    (comp (ref "USB1")
      (value "USB_MICRO_AB")
      (footprint "eagle-import:USB_MICRO_AB")
      (libsource (lib "eagle-import") (part "USB_MICRO_AB"))
    )
    (comp (ref "USB2")
      (value "USB_MICRO_AB")
      (footprint "eagle-import:USB_MICRO_AB")
      (libsource (lib "eagle-import") (part "USB_MICRO_AB"))
    )
    (comp (ref "USB_SENSE")
      (value "2P-HEADER-JUMPER")
      (footprint "eagle-import:1X02")
      (libsource (lib "eagle-import") (part "2P-HEADER-JUMPER"))
    )
    (comp (ref "WCLK")
      (value "2P-HEADER-JUMPER")
      (footprint "eagle-import:1X02")
      (libsource (lib "eagle-import") (part "2P-HEADER-JUMPER"))
    )
    (comp (ref "X1")
      (value "48MHz")
      (footprint "eagle-import:ABM3C")
      (libsource (lib "eagle-import") (part "XTAL-ABRACONABM3C"))
    )
    (comp (ref "X3")
      (value "12MHz")
      (footprint "eagle-import:ABM8G")
      (libsource (lib "eagle-import") (part "XTAL-ABRACONABM8G"))
    )
  )
  (nets
    (net (code "1") (name "/AGND") (class "Default")
      (node (ref "C31") (pin "2") (pinfunction "2_2") (pintype "passive"))
      (node (ref "C33") (pin "2") (pinfunction "2_2") (pintype "passive"))
      (node (ref "C34") (pin "2") (pinfunction "2_2") (pintype "passive"))
      (node (ref "C40") (pin "2") (pinfunction "2_2") (pintype "passive"))
      (node (ref "C41") (pin "2") (pinfunction "2_2") (pintype "passive"))
      (node (ref "C42") (pin "2") (pinfunction "2_2") (pintype "passive"))
      (node (ref "C48") (pin "2") (pinfunction "2_2") (pintype "passive"))
      (node (ref "C50") (pin "2") (pinfunction "2_2") (pintype "passive"))
      (node (ref "LINE_IN") (pin "5") (pinfunction "GND_5") (pintype "bidirectional"))
      (node (ref "PHONE_OUT") (pin "5") (pinfunction "GND_5") (pintype "bidirectional"))
      (node (ref "R23") (pin "1") (pinfunction "1_1") (pintype "passive"))
      (node (ref "R25") (pin "1") (pinfunction "1_1") (pintype "passive"))
      (node (ref "U3") (pin "17") (pinfunction "AVSS_17") (pintype "bidirectional"))
      (node (ref "U9") (pin "2") (pinfunction "VSS_2") (pintype "bidirectional"))
    )
    (net (code "2") (name "/AUX_VDD") (class "Default")
      (node (ref "C63") (pin "1") (pinfunction "1_1") (pintype "passive"))
      (node (ref "C64") (pin "1") (pinfunction "1_1") (pintype "passive"))
      (node (ref "C65") (pin "1") (pinfunction "1_1") (pintype "passive"))
      (node (ref "L18") (pin "1") (pinfunction "1_1") (pintype "passive"))
      (node (ref "LED_LL") (pin "2") (pinfunction "A_2") (pintype "passive"))
      (node (ref "LED_LL") (pin "2-2") (pinfunction "A_2-2") (pintype "passive"))
      (node (ref "LED_LR") (pin "2") (pinfunction "A_2") (pintype "passive"))
      (node (ref "LED_LR") (pin "2-2") (pinfunction "A_2-2") (pintype "passive"))
      (node (ref "LED_UL") (pin "2") (pinfunction "A_2") (pintype "passive"))
      (node (ref "LED_UL") (pin "2-2") (pinfunction "A_2-2") (pintype "passive"))
      (node (ref "LED_UR") (pin "2") (pinfunction "A_2") (pintype "passive"))
      (node (ref "LED_UR") (pin "2-2") (pinfunction "A_2-2") (pintype "passive"))
      (node (ref "R36") (pin "2") (pinfunction "2_2") (pintype "passive"))
      (node (ref "U8") (pin "18") (pinfunction "VDD_18") (pintype "bidirectional"))
      (node (ref "U8") (pin "4") (pinfunction "VDD_4") (pintype "bidirectional"))
    )
    (net (code "3") (name "/AUX_VSS") (class "Default")
      (node (ref "C63") (pin "2") (pinfunction "2_2") (pintype "passive"))
      (node (ref "C64") (pin "2") (pinfunction "2_2") (pintype "passive"))
      (node (ref "Q2") (pin "2") (pinfunction "S_2") (pintype "passive"))
      (node (ref "Q3") (pin "2") (pinfunction "S_2") (pintype "passive"))
      (node (ref "Q4") (pin "2") (pinfunction "S_2") (pintype "passive"))
      (node (ref "Q5") (pin "2") (pinfunction "S_2") (pintype "passive"))
      (node (ref "Q6") (pin "2") (pinfunction "S_2") (pintype "passive"))
      (node (ref "Q7") (pin "2") (pinfunction "S_2") (pintype "passive"))
      (node (ref "U8") (pin "21") (pinfunction "VSS_21") (pintype "bidirectional"))
      (node (ref "U8") (pin "5") (pinfunction "VSS_5") (pintype "bidirectional"))
    )
    (net (code "4") (name "/AUX_~{CHANGE}") (class "Default")
      (node (ref "!CHANGE") (pin "1") (pinfunction "P$1_1") (pintype "bidirectional"))
      (node (ref "U8") (pin "28") (pinfunction "~{CHANGE}_28") (pintype "bidirectional"))
    )
    (net (code "5") (name "/AVDD") (class "Default")
      (node (ref "C10") (pin "1") (pinfunction "1_1") (pintype "passive"))
      (node (ref "C11") (pin "1") (pinfunction "1_1") (pintype "passive"))
      (node (ref "C12") (pin "1") (pinfunction "1_1") (pintype "passive"))
      (node (ref "C15") (pin "1") (pinfunction "1_1") (pintype "passive"))
      (node (ref "C16") (pin "1") (pinfunction "1_1") (pintype "passive"))
      (node (ref "C17") (pin "1") (pinfunction "1_1") (pintype "passive"))
      (node (ref "C18") (pin "1") (pinfunction "1_1") (pintype "passive"))
      (node (ref "C19") (pin "1") (pinfunction "1_1") (pintype "passive"))
      (node (ref "C2") (pin "1") (pinfunction "1_1") (pintype "passive"))
      (node (ref "C20") (pin "1") (pinfunction "1_1") (pintype "passive"))
      (node (ref "C21") (pin "1") (pinfunction "1_1") (pintype "passive"))
      (node (ref "C22") (pin "1") (pinfunction "1_1") (pintype "passive"))
      (node (ref "C8") (pin "1") (pinfunction "1_1") (pintype "passive"))
      (node (ref "C9") (pin "1") (pinfunction "1_1") (pintype "passive"))
      (node (ref "L2") (pin "1") (pinfunction "1_1") (pintype "passive"))
      (node (ref "L3") (pin "1") (pinfunction "1_1") (pintype "passive"))
      (node (ref "R9") (pin "2") (pinfunction "2_2") (pintype "passive"))
      (node (ref "U1") (pin "20") (pinfunction "AVDD1_20") (pintype "bidirectional"))
      (node (ref "U1") (pin "23") (pinfunction "AVDD2_23") (pintype "bidirectional"))
      (node (ref "U1") (pin "26") (pinfunction "AVDD3_26") (pintype "bidirectional"))
      (node (ref "U1") (pin "27") (pinfunction "AVDD4_27") (pintype "bidirectional"))
      (node (ref "U1") (pin "28") (pinfunction "AVDD5_28") (pintype "bidirectional"))
      (node (ref "U1") (pin "31") (pinfunction "AVDD6_31") (pintype "bidirectional"))
      (node (ref "U2") (pin "1") (pinfunction "AVDD_PA1_1") (pintype "bidirectional"))
      (node (ref "U2") (pin "10") (pinfunction "AVDD_PA2_10") (pintype "bidirectional"))
      (node (ref "U2") (pin "13") (pinfunction "AVDD_LNA_13") (pintype "bidirectional"))
      (node (ref "U2") (pin "16") (pinfunction "AVDD_BIAS_16") (pintype "bidirectional"))
    )
    (net (code "6") (name "/AVDD_CODEC") (class "Default")
      (node (ref "C31") (pin "1") (pinfunction "1_1") (pintype "passive"))
      (node (ref "C34") (pin "1") (pinfunction "1_1") (pintype "passive"))
      (node (ref "C40") (pin "1") (pinfunction "1_1") (pintype "passive"))
      (node (ref "C41") (pin "1") (pinfunction "1_1") (pintype "passive"))
      (node (ref "C42") (pin "1") (pinfunction "1_1") (pintype "passive"))
      (node (ref "L14") (pin "1") (pinfunction "1_1") (pintype "passive"))
      (node (ref "R22") (pin "2") (pinfunction "2_2") (pintype "passive"))
      (node (ref "R24") (pin "2") (pinfunction "2_2") (pintype "passive"))
      (node (ref "R31") (pin "2") (pinfunction "2_2") (pintype "passive"))
      (node (ref "U3") (pin "26") (pinfunction "LDOIN_26") (pintype "bidirectional"))
      (node (ref "U9") (pin "6") (pinfunction "VDD_6") (pintype "bidirectional"))
    )
    (net (code "7") (name "/AVR_VDD") (class "Default")
      (node (ref "C35") (pin "1") (pinfunction "1_1") (pintype "passive"))
      (node (ref "C46") (pin "1") (pinfunction "1_1") (pintype "passive"))
      (node (ref "C47") (pin "1") (pinfunction "1_1") (pintype "passive"))
      (node (ref "C69") (pin "1") (pinfunction "1_1") (pintype "passive"))
      (node (ref "ERASE") (pin "3") (pinfunction "3_3") (pintype "bidirectional"))
      (node (ref "JTAG") (pin "1") (pinfunction "1_1") (pintype "bidirectional"))
      (node (ref "L16") (pin "1") (pinfunction "1_1") (pintype "passive"))
      (node (ref "R11") (pin "2") (pinfunction "2_2") (pintype "passive"))
      (node (ref "R14") (pin "2") (pinfunction "2_2") (pintype "passive"))
      (node (ref "R43") (pin "1") (pinfunction "1_1") (pintype "passive"))
      (node (ref "R44") (pin "2") (pinfunction "2_2") (pintype "passive"))
      (node (ref "R45") (pin "2") (pinfunction "2_2") (pintype "passive"))
      (node (ref "R46") (pin "2") (pinfunction "2_2") (pintype "passive"))
      (node (ref "R47") (pin "2") (pinfunction "2_2") (pintype "passive"))
      (node (ref "R6") (pin "2") (pinfunction "2_2") (pintype "passive"))
      (node (ref "SD_VDD") (pin "2") (pinfunction "P$2_2") (pintype "bidirectional"))
      (node (ref "U7") (pin "105") (pinfunction "VDDIO_3_105") (pintype "bidirectional"))
      (node (ref "U7") (pin "11") (pinfunction "VDDIO_1_11") (pintype "bidirectional"))
      (node (ref "U7") (pin "125") (pinfunction "VDDIO_4_125") (pintype "bidirectional"))
      (node (ref "U7") (pin "41") (pinfunction "VDDUTMI_41") (pintype "bidirectional"))
      (node (ref "U7") (pin "52") (pinfunction "VDDBU_52") (pintype "bidirectional"))
      (node (ref "U7") (pin "57") (pinfunction "VDDIN_57") (pintype "bidirectional"))
      (node (ref "U7") (pin "62") (pinfunction "VDDIO_2_62") (pintype "bidirectional"))
      (node (ref "U7") (pin "73") (pinfunction "VDDANA_73") (pintype "bidirectional"))
      (node (ref "U7") (pin "75") (pinfunction "ADVREF_75") (pintype "bidirectional"))
    )
    (net (code "8") (name "/DVDD_CODEC") (class "Default")
      (node (ref "C32") (pin "1") (pinfunction "1_1") (pintype "passive"))
      (node (ref "C45") (pin "1") (pinfunction "1_1") (pintype "passive"))
      (node (ref "L15") (pin "1") (pinfunction "1_1") (pintype "passive"))
      (node (ref "U3") (pin "12") (pinfunction "SPI_SELECT_12") (pintype "bidirectional"))
      (node (ref "U3") (pin "30") (pinfunction "LDO_SELECT_30") (pintype "bidirectional"))
      (node (ref "U3") (pin "6") (pinfunction "IOVDD_6") (pintype "bidirectional"))
    )
    (net (code "9") (name "/IOVDD") (class "Default")
      (node (ref "C1") (pin "1") (pinfunction "1_1") (pintype "passive"))
      (node (ref "C3") (pin "1") (pinfunction "1_1") (pintype "passive"))
      (node (ref "C4") (pin "1") (pinfunction "1_1") (pintype "passive"))
      (node (ref "C5") (pin "1") (pinfunction "1_1") (pintype "passive"))
      (node (ref "C6") (pin "1") (pinfunction "1_1") (pintype "passive"))
      (node (ref "C7") (pin "1") (pinfunction "1_1") (pintype "passive"))
      (node (ref "CC8531") (pin "A") (pinfunction "A_A") (pintype "passive"))
      (node (ref "L1") (pin "1") (pinfunction "1_1") (pintype "passive"))
      (node (ref "U1") (pin "10") (pinfunction "IOVDD1_10") (pintype "bidirectional"))
      (node (ref "U1") (pin "12") (pinfunction "IOVDD2_12") (pintype "bidirectional"))
      (node (ref "U1") (pin "18") (pinfunction "IOVDD3_18") (pintype "bidirectional"))
      (node (ref "U1") (pin "37") (pinfunction "IOVDD4_37") (pintype "bidirectional"))
      (node (ref "U1") (pin "40") (pinfunction "DVDD_40") (pintype "bidirectional"))
    )
    (net (code "10") (name "/VBUS") (class "Default")
      (node (ref "C51") (pin "1") (pinfunction "1_1") (pintype "passive"))
      (node (ref "R18") (pin "2") (pinfunction "2_2") (pintype "passive"))
      (node (ref "U6") (pin "11") (pinfunction "VBUS_11") (pintype "bidirectional"))
      (node (ref "U6") (pin "13") (pinfunction "D0_13") (pintype "bidirectional"))
      (node (ref "U7") (pin "39") (pinfunction "VBUS_39") (pintype "bidirectional"))
      (node (ref "USB1") (pin "1") (pinfunction "VBUS_1") (pintype "bidirectional"))
      (node (ref "USB2") (pin "1") (pinfunction "VBUS_1") (pintype "bidirectional"))
    )
    (net (code "11") (name "/VDDCORE") (class "Default")
      (node (ref "C43") (pin "1") (pinfunction "1_1") (pintype "passive"))
      (node (ref "C44") (pin "1") (pinfunction "1_1") (pintype "passive"))
      (node (ref "U7") (pin "10") (pinfunction "VDDCORE_1_10") (pintype "bidirectional"))
      (node (ref "U7") (pin "104") (pinfunction "VDDCORE_4_104") (pintype "bidirectional"))
      (node (ref "U7") (pin "124") (pinfunction "VDDCORE_5_124") (pintype "bidirectional"))
      (node (ref "U7") (pin "34") (pinfunction "VDDPLL_34") (pintype "bidirectional"))
      (node (ref "U7") (pin "45") (pinfunction "VDDCORE_2_45") (pintype "bidirectional"))
      (node (ref "U7") (pin "56") (pinfunction "VDDOUT_56") (pintype "bidirectional"))
      (node (ref "U7") (pin "61") (pinfunction "VDDCORE_3_61") (pintype "bidirectional"))
    )
    (net (code "12") (name "/X_~{PAIR}") (class "Default")
      (node (ref "!PAIR") (pin "1") (pinfunction "P$1_1") (pintype "bidirectional"))
      (node (ref "U1") (pin "7") (pinfunction "GIO1_7") (pintype "bidirectional"))
    )
    (net (code "13") (name "/~{AVR_LED2}") (class "Default")
      (node (ref "AVR1") (pin "C") (pinfunction "C_C") (pintype "passive"))
      (node (ref "U7") (pin "68") (pinfunction "PB27_68") (pintype "bidirectional"))
    )
    (net (code "14") (name "/~{AVR_LED3}") (class "Default")
      (node (ref "AVR2") (pin "C") (pinfunction "C_C") (pintype "passive"))
      (node (ref "U7") (pin "71") (pinfunction "PA19_71") (pintype "bidirectional"))
    )
    (net (code "15") (name "/~{AVR_LED}") (class "Default")
      (node (ref "AVR") (pin "C") (pinfunction "C_C") (pintype "passive"))
      (node (ref "U7") (pin "72") (pinfunction "PA20_72") (pintype "bidirectional"))
    )
    (net (code "16") (name "/~{CHANGE}") (class "Default")
      (node (ref "!CHANGE") (pin "2") (pinfunction "P$2_2") (pintype "bidirectional"))
      (node (ref "U7") (pin "32") (pinfunction "PD10_32") (pintype "bidirectional"))
    )
    (net (code "17") (name "/~{PAIR}") (class "Default")
      (node (ref "!PAIR") (pin "2") (pinfunction "P$2_2") (pintype "bidirectional"))
      (node (ref "U7") (pin "21") (pinfunction "PD8_21") (pintype "bidirectional"))
    )
    (net (code "18") (name "/~{RESET}") (class "Default")
      (node (ref "C69") (pin "2") (pinfunction "2_2") (pintype "passive"))
      (node (ref "JTAG") (pin "10") (pinfunction "10_10") (pintype "bidirectional"))
      (node (ref "R46") (pin "1") (pinfunction "1_1") (pintype "passive"))
      (node (ref "RESET") (pin "1") (pinfunction "1_1") (pintype "bidirectional"))
      (node (ref "U7") (pin "47") (pinfunction "NRSTB_47") (pintype "bidirectional"))
    )
    (net (code "19") (name "/~{SD_CARD}") (class "Default")
      (node (ref "!SD_CARD") (pin "1") (pinfunction "P$1_1") (pintype "bidirectional"))
      (node (ref "U7") (pin "66") (pinfunction "PC8_66") (pintype "bidirectional"))
    )
    (net (code "20") (name "3.3V") (class "Default")
      (node (ref "AMP_AVDD") (pin "2") (pinfunction "P$2_2") (pintype "bidirectional"))
      (node (ref "AUX_VDD") (pin "2") (pinfunction "P$2_2") (pintype "bidirectional"))
      (node (ref "AVR_VDD") (pin "2") (pinfunction "P$2_2") (pintype "bidirectional"))
      (node (ref "C53") (pin "1") (pinfunction "1_1") (pintype "passive"))
      (node (ref "CC8531_AVDD") (pin "2") (pinfunction "P$2_2") (pintype "bidirectional"))
      (node (ref "CC8531_IOVDD") (pin "2") (pinfunction "P$2_2") (pintype "bidirectional"))
      (node (ref "CC_DEBUG") (pin "2") (pinfunction "2_2") (pintype "bidirectional"))
      (node (ref "CODEC_AVDD") (pin "2") (pinfunction "P$2_2") (pintype "bidirectional"))
      (node (ref "CODEC_DVDD") (pin "2") (pinfunction "P$2_2") (pintype "bidirectional"))
      (node (ref "EXT") (pin "1") (pinfunction "P$1_1") (pintype "bidirectional"))
      (node (ref "R3") (pin "2") (pinfunction "2_2") (pintype "passive"))
      (node (ref "U5") (pin "3") (pinfunction "VOUT_3") (pintype "bidirectional"))
    )
    (net (code "21") (name "AUDIO") (class "Default")
      (node (ref "AUDIO") (pin "2") (pinfunction "P$2_2") (pintype "bidirectional"))
      (node (ref "U7") (pin "85") (pinfunction "PA2_85") (pintype "bidirectional"))
    )
    (net (code "22") (name "AUX_BLUE_BOT") (class "Default")
      (node (ref "BLUE_BOT") (pin "1") (pinfunction "P$1_1") (pintype "bidirectional"))
      (node (ref "Q7") (pin "1") (pinfunction "G_1") (pintype "passive"))
    )
    (net (code "23") (name "AUX_BLUE_TOP") (class "Default")
      (node (ref "BLUE_TOP") (pin "1") (pinfunction "P$1_1") (pintype "bidirectional"))
      (node (ref "Q4") (pin "1") (pinfunction "G_1") (pintype "passive"))
    )
    (net (code "24") (name "AUX_CS") (class "Default")
      (node (ref "AUX_CS") (pin "1") (pinfunction "P$1_1") (pintype "bidirectional"))
      (node (ref "U8") (pin "14") (pinfunction "~{SS}_14") (pintype "bidirectional"))
    )
    (net (code "25") (name "AUX_GREEN_BOT") (class "Default")
      (node (ref "GREEN_BOT") (pin "1") (pinfunction "P$1_1") (pintype "bidirectional"))
      (node (ref "Q6") (pin "1") (pinfunction "G_1") (pintype "passive"))
    )
    (net (code "26") (name "AUX_GREEN_TOP") (class "Default")
      (node (ref "GREEN_TOP") (pin "1") (pinfunction "P$1_1") (pintype "bidirectional"))
      (node (ref "Q3") (pin "1") (pinfunction "G_1") (pintype "passive"))
    )
    (net (code "27") (name "AUX_MISO") (class "Default")
      (node (ref "AUX_MISO") (pin "1") (pinfunction "P$1_1") (pintype "bidirectional"))
      (node (ref "U8") (pin "16") (pinfunction "MISO_16") (pintype "bidirectional"))
    )
    (net (code "28") (name "AUX_MOSI") (class "Default")
      (node (ref "AUX_MOSI") (pin "1") (pinfunction "P$1_1") (pintype "bidirectional"))
      (node (ref "U8") (pin "15") (pinfunction "MOSI_15") (pintype "bidirectional"))
    )
    (net (code "29") (name "AUX_RED_BOT") (class "Default")
      (node (ref "Q5") (pin "1") (pinfunction "G_1") (pintype "passive"))
      (node (ref "RED_BOT") (pin "1") (pinfunction "P$1_1") (pintype "bidirectional"))
    )
    (net (code "30") (name "AUX_RED_TOP") (class "Default")
      (node (ref "Q2") (pin "1") (pinfunction "G_1") (pintype "passive"))
      (node (ref "RED_TOP") (pin "1") (pinfunction "P$1_1") (pintype "bidirectional"))
    )
    (net (code "31") (name "AUX_SCLK") (class "Default")
      (node (ref "AUX_SCLK") (pin "1") (pinfunction "P$1_1") (pintype "bidirectional"))
      (node (ref "U8") (pin "17") (pinfunction "SCK_17") (pintype "bidirectional"))
    )
    (net (code "32") (name "BCLK") (class "Default")
      (node (ref "BCLK") (pin "1") (pinfunction "P$1_1") (pintype "bidirectional"))
      (node (ref "CC8531_BCLK") (pin "2") (pinfunction "P$2_2") (pintype "bidirectional"))
      (node (ref "U3") (pin "2") (pinfunction "BCLK_2") (pintype "bidirectional"))
    )
    (net (code "33") (name "BLUE_BOT") (class "Default")
      (node (ref "BLUE_BOT") (pin "2") (pinfunction "P$2_2") (pintype "bidirectional"))
      (node (ref "U7") (pin "135") (pinfunction "PC24_135") (pintype "bidirectional"))
    )
    (net (code "34") (name "BLUE_TOP") (class "Default")
      (node (ref "BLUE_TOP") (pin "2") (pinfunction "P$2_2") (pintype "bidirectional"))
      (node (ref "U7") (pin "134") (pinfunction "PC23_134") (pintype "bidirectional"))
    )
    (net (code "35") (name "CS_CC8531") (class "Default")
      (node (ref "CC8531_CS") (pin "2") (pinfunction "P$2_2") (pintype "bidirectional"))
      (node (ref "U7") (pin "22") (pinfunction "PD9_22") (pintype "bidirectional"))
    )
    (net (code "36") (name "CS_CODEC") (class "Default")
      (node (ref "CODEC_CS") (pin "2") (pinfunction "P$2_2") (pintype "bidirectional"))
      (node (ref "U7") (pin "15") (pinfunction "PD2_15") (pintype "bidirectional"))
    )
    (net (code "37") (name "CS_SD") (class "Default")
      (node (ref "SD_CS") (pin "1") (pinfunction "P$1_1") (pintype "bidirectional"))
      (node (ref "U7") (pin "67") (pinfunction "PC9_67") (pintype "bidirectional"))
    )
    (net (code "38") (name "CS_TOUCH") (class "Default")
      (node (ref "AUX_CS") (pin "2") (pinfunction "P$2_2") (pintype "bidirectional"))
      (node (ref "U7") (pin "26") (pinfunction "PA7_26") (pintype "bidirectional"))
    )
    (net (code "39") (name "C_AUDIO") (class "Default")
      (node (ref "AUDIO") (pin "1") (pinfunction "P$1_1") (pintype "bidirectional"))
      (node (ref "C36") (pin "1") (pinfunction "1_1") (pintype "passive"))
      (node (ref "R12") (pin "1") (pinfunction "1_1") (pintype "passive"))
      (node (ref "U9") (pin "7") (pinfunction "OUTA_7") (pintype "bidirectional"))
    )
    (net (code "40") (name "C_CS_CODEC") (class "Default")
      (node (ref "CODEC_CS") (pin "1") (pinfunction "P$1_1") (pintype "bidirectional"))
      (node (ref "U3") (pin "9") (pinfunction "SCL/SSZ_9") (pintype "bidirectional"))
    )
    (net (code "41") (name "C_LINEIN_SENSE") (class "Default")
      (node (ref "LINEIN_SENSE") (pin "1") (pinfunction "P$1_1") (pintype "bidirectional"))
      (node (ref "LINE_IN") (pin "3") (pinfunction "L_SW_3") (pintype "bidirectional"))
      (node (ref "R22") (pin "1") (pinfunction "1_1") (pintype "passive"))
    )
    (net (code "42") (name "C_MISO") (class "Default")
      (node (ref "CODEC_MISO") (pin "1") (pinfunction "P$1_1") (pintype "bidirectional"))
      (node (ref "U3") (pin "11") (pinfunction "MISO/MFP4_11") (pintype "bidirectional"))
    )
    (net (code "43") (name "C_MOSI") (class "Default")
      (node (ref "CODEC_MOSI") (pin "1") (pinfunction "P$1_1") (pintype "bidirectional"))
      (node (ref "U3") (pin "10") (pinfunction "SDA/MOSI_10") (pintype "bidirectional"))
    )
    (net (code "44") (name "C_PHONE_SENSE") (class "Default")
      (node (ref "PHONE_OUT") (pin "3") (pinfunction "L_SW_3") (pintype "bidirectional"))
      (node (ref "PHONE_SENSE") (pin "1") (pinfunction "P$1_1") (pintype "bidirectional"))
      (node (ref "R24") (pin "1") (pinfunction "1_1") (pintype "passive"))
    )
    (net (code "45") (name "C_RESET_CODEC") (class "Default")
      (node (ref "CODEC_RESET") (pin "1") (pinfunction "P$1_1") (pintype "bidirectional"))
      (node (ref "U3") (pin "31") (pinfunction "~{RESET}_31") (pintype "bidirectional"))
    )
    (net (code "46") (name "C_SCLK") (class "Default")
      (node (ref "CODEC_SCLK") (pin "1") (pinfunction "P$1_1") (pintype "bidirectional"))
      (node (ref "U3") (pin "8") (pinfunction "SCLK/MFP3_8") (pintype "bidirectional"))
    )
    (net (code "47") (name "D+_CC8531") (class "Default")
      (node (ref "R2") (pin "2") (pinfunction "2_2") (pintype "passive"))
      (node (ref "R7") (pin "2") (pinfunction "2_2") (pintype "passive"))
      (node (ref "USB1") (pin "3") (pinfunction "D+_3") (pintype "bidirectional"))
    )
    (net (code "48") (name "D+_UC") (class "Default")
      (node (ref "R42") (pin "2") (pinfunction "2_2") (pintype "passive"))
      (node (ref "U7") (pin "37") (pinfunction "DHSDP_37") (pintype "bidirectional"))
      (node (ref "USB2") (pin "3") (pinfunction "D+_3") (pintype "bidirectional"))
    )
    (net (code "49") (name "D-_CC8531") (class "Default")
      (node (ref "R1") (pin "2") (pinfunction "2_2") (pintype "passive"))
      (node (ref "USB1") (pin "2") (pinfunction "D-_2") (pintype "bidirectional"))
    )
    (net (code "50") (name "D-_UC") (class "Default")
      (node (ref "R41") (pin "2") (pinfunction "2_2") (pintype "passive"))
      (node (ref "U7") (pin "38") (pinfunction "DHSDM_38") (pintype "bidirectional"))
      (node (ref "USB2") (pin "2") (pinfunction "D-_2") (pintype "bidirectional"))
    )
    (net (code "51") (name "DIN") (class "Default")
      (node (ref "CC8531_DIN") (pin "2") (pinfunction "P$2_2") (pintype "bidirectional"))
      (node (ref "DIN") (pin "1") (pinfunction "P$1_1") (pintype "bidirectional"))
      (node (ref "U3") (pin "4") (pinfunction "DIN/MFP1_4") (pintype "bidirectional"))
    )
    (net (code "52") (name "DOUT") (class "Default")
      (node (ref "CC8531_DOUT") (pin "2") (pinfunction "P$2_2") (pintype "bidirectional"))
      (node (ref "DOUT") (pin "1") (pinfunction "P$1_1") (pintype "bidirectional"))
      (node (ref "U3") (pin "5") (pinfunction "DOUT/MFP2_5") (pintype "bidirectional"))
    )
    (net (code "53") (name "ERASE") (class "Default")
      (node (ref "ERASE") (pin "1") (pinfunction "1_1") (pintype "bidirectional"))
      (node (ref "U7") (pin "130") (pinfunction "PC0_130") (pintype "bidirectional"))
    )
    (net (code "54") (name "GND") (class "Default")
      (node (ref "BATTERY") (pin "-") (pinfunction "N_-") (pintype "passive"))
      (node (ref "BATTERY") (pin "X1") (pinfunction "CASE_X1") (pintype "passive"))
      (node (ref "BATTERY") (pin "X2") (pinfunction "CASE_X2") (pintype "passive"))
      (node (ref "C1") (pin "2") (pinfunction "2_2") (pintype "passive"))
      (node (ref "C10") (pin "2") (pinfunction "2_2") (pintype "passive"))
      (node (ref "C11") (pin "2") (pinfunction "2_2") (pintype "passive"))
      (node (ref "C12") (pin "2") (pinfunction "2_2") (pintype "passive"))
      (node (ref "C13") (pin "2") (pinfunction "2_2") (pintype "passive"))
      (node (ref "C14") (pin "2") (pinfunction "2_2") (pintype "passive"))
      (node (ref "C15") (pin "2") (pinfunction "2_2") (pintype "passive"))
      (node (ref "C16") (pin "2") (pinfunction "2_2") (pintype "passive"))
      (node (ref "C17") (pin "2") (pinfunction "2_2") (pintype "passive"))
      (node (ref "C18") (pin "2") (pinfunction "2_2") (pintype "passive"))
      (node (ref "C19") (pin "2") (pinfunction "2_2") (pintype "passive"))
      (node (ref "C2") (pin "2") (pinfunction "2_2") (pintype "passive"))
      (node (ref "C20") (pin "2") (pinfunction "2_2") (pintype "passive"))
      (node (ref "C21") (pin "2") (pinfunction "2_2") (pintype "passive"))
      (node (ref "C22") (pin "2") (pinfunction "2_2") (pintype "passive"))
      (node (ref "C23") (pin "2") (pinfunction "2_2") (pintype "passive"))
      (node (ref "C24") (pin "2") (pinfunction "2_2") (pintype "passive"))
      (node (ref "C27") (pin "2") (pinfunction "2_2") (pintype "passive"))
      (node (ref "C28") (pin "2") (pinfunction "2_2") (pintype "passive"))
      (node (ref "C29") (pin "2") (pinfunction "2_2") (pintype "passive"))
      (node (ref "C3") (pin "2") (pinfunction "2_2") (pintype "passive"))
      (node (ref "C30") (pin "2") (pinfunction "2_2") (pintype "passive"))
      (node (ref "C32") (pin "2") (pinfunction "2_2") (pintype "passive"))
      (node (ref "C35") (pin "2") (pinfunction "2_2") (pintype "passive"))
      (node (ref "C4") (pin "2") (pinfunction "2_2") (pintype "passive"))
      (node (ref "C43") (pin "2") (pinfunction "2_2") (pintype "passive"))
      (node (ref "C44") (pin "2") (pinfunction "2_2") (pintype "passive"))
      (node (ref "C45") (pin "2") (pinfunction "2_2") (pintype "passive"))
      (node (ref "C46") (pin "2") (pinfunction "2_2") (pintype "passive"))
      (node (ref "C47") (pin "2") (pinfunction "2_2") (pintype "passive"))
      (node (ref "C49") (pin "2") (pinfunction "2_2") (pintype "passive"))
      (node (ref "C5") (pin "2") (pinfunction "2_2") (pintype "passive"))
      (node (ref "C51") (pin "2") (pinfunction "2_2") (pintype "passive"))
      (node (ref "C52") (pin "2") (pinfunction "2_2") (pintype "passive"))
      (node (ref "C53") (pin "2") (pinfunction "2_2") (pintype "passive"))
      (node (ref "C54") (pin "2") (pinfunction "2_2") (pintype "passive"))
      (node (ref "C56") (pin "2") (pinfunction "2_2") (pintype "passive"))
      (node (ref "C6") (pin "2") (pinfunction "2_2") (pintype "passive"))
      (node (ref "C65") (pin "2") (pinfunction "2_2") (pintype "passive"))
      (node (ref "C68") (pin "2") (pinfunction "2_2") (pintype "passive"))
      (node (ref "C7") (pin "2") (pinfunction "2_2") (pintype "passive"))
      (node (ref "C8") (pin "2") (pinfunction "2_2") (pintype "passive"))
      (node (ref "C9") (pin "2") (pinfunction "2_2") (pintype "passive"))
      (node (ref "CC_DEBUG") (pin "1") (pinfunction "1_1") (pintype "bidirectional"))
      (node (ref "JTAG") (pin "3") (pinfunction "3_3") (pintype "bidirectional"))
      (node (ref "JTAG") (pin "5") (pinfunction "5_5") (pintype "bidirectional"))
      (node (ref "JTAG") (pin "9") (pinfunction "9_9") (pintype "bidirectional"))
      (node (ref "L10") (pin "1") (pinfunction "1_1") (pintype "passive"))
      (node (ref "MICROSD1") (pin "GND1") (pinfunction "GND_GND1") (pintype "bidirectional"))
      (node (ref "MICROSD1") (pin "GND2") (pinfunction "GND_GND2") (pintype "bidirectional"))
      (node (ref "MICROSD1") (pin "GND3") (pinfunction "GND_GND3") (pintype "bidirectional"))
      (node (ref "MICROSD1") (pin "GND4") (pinfunction "GND_GND4") (pintype "bidirectional"))
      (node (ref "MICROSD1") (pin "SWB") (pinfunction "SWB_SWB") (pintype "bidirectional"))
      (node (ref "MICROSD1") (pin "VSS") (pinfunction "GND_VSS") (pintype "bidirectional"))
      (node (ref "POWER") (pin "C") (pinfunction "C_C") (pintype "passive"))
      (node (ref "R10") (pin "1") (pinfunction "1_1") (pintype "passive"))
      (node (ref "R20") (pin "1") (pinfunction "1_1") (pintype "passive"))
      (node (ref "R21") (pin "1") (pinfunction "1_1") (pintype "passive"))
      (node (ref "R32") (pin "1") (pinfunction "1_1") (pintype "passive"))
      (node (ref "R4") (pin "1") (pinfunction "1_1") (pintype "passive"))
      (node (ref "R8") (pin "1") (pinfunction "1_1") (pintype "passive"))
      (node (ref "RESET") (pin "3") (pinfunction "3_3") (pintype "bidirectional"))
      (node (ref "SMA") (pin "GND1") (pinfunction "GND_GND1") (pintype "bidirectional"))
      (node (ref "SMA") (pin "GND2") (pinfunction "GND_GND2") (pintype "bidirectional"))
      (node (ref "SMA") (pin "GND3") (pinfunction "GND_GND3") (pintype "bidirectional"))
      (node (ref "SMA") (pin "GND4") (pinfunction "GND_GND4") (pintype "bidirectional"))
      (node (ref "U1") (pin "29") (pinfunction "VBAT_29") (pintype "bidirectional"))
      (node (ref "U1") (pin "34") (pinfunction "GIO12_34") (pintype "bidirectional"))
      (node (ref "U1") (pin "35") (pinfunction "GIO13_35") (pintype "bidirectional"))
      (node (ref "U1") (pin "8") (pinfunction "GIO2_8") (pintype "bidirectional"))
      (node (ref "U1") (pin "GND") (pinfunction "GND_GND") (pintype "bidirectional"))
      (node (ref "U2") (pin "12") (pinfunction "GND_12") (pintype "bidirectional"))
      (node (ref "U2") (pin "14") (pinfunction "GND_14") (pintype "bidirectional"))
      (node (ref "U2") (pin "8") (pinfunction "GND_8") (pintype "bidirectional"))
      (node (ref "U2") (pin "9") (pinfunction "GND_9") (pintype "bidirectional"))
      (node (ref "U2") (pin "GND") (pinfunction "GND_GND") (pintype "bidirectional"))
      (node (ref "U3") (pin "28") (pinfunction "DVSS_28") (pintype "bidirectional"))
      (node (ref "U3") (pin "7") (pinfunction "IOVSS_7") (pintype "bidirectional"))
      (node (ref "U3") (pin "GND") (pinfunction "GND_GND") (pintype "bidirectional"))
      (node (ref "U5") (pin "2") (pinfunction "GND_2") (pintype "bidirectional"))
      (node (ref "U5") (pin "4") (pinfunction "GND_4") (pintype "bidirectional"))
      (node (ref "U6") (pin "1") (pinfunction "NTC_1") (pintype "bidirectional"))
      (node (ref "U6") (pin "14") (pinfunction "D1_14") (pintype "bidirectional"))
      (node (ref "U6") (pin "4") (pinfunction "D2_4") (pintype "bidirectional"))
      (node (ref "U6") (pin "GND") (pinfunction "GND_GND") (pintype "bidirectional"))
      (node (ref "U7") (pin "106") (pinfunction "GND_3_106") (pintype "bidirectional"))
      (node (ref "U7") (pin "12") (pinfunction "GND_1_12") (pintype "bidirectional"))
      (node (ref "U7") (pin "126") (pinfunction "GND_4_126") (pintype "bidirectional"))
      (node (ref "U7") (pin "33") (pinfunction "GNDPLL_33") (pintype "bidirectional"))
      (node (ref "U7") (pin "44") (pinfunction "GNDUTMI_44") (pintype "bidirectional"))
      (node (ref "U7") (pin "46") (pinfunction "JTAGSEL_46") (pintype "bidirectional"))
      (node (ref "U7") (pin "54") (pinfunction "GNDBU_54") (pintype "bidirectional"))
      (node (ref "U7") (pin "58") (pinfunction "GND_2_58") (pintype "bidirectional"))
      (node (ref "U7") (pin "74") (pinfunction "GNDANA_74") (pintype "bidirectional"))
      (node (ref "USB1") (pin "5") (pinfunction "GND_5") (pintype "bidirectional"))
      (node (ref "USB1") (pin "GND1") (pinfunction "GND_GND1") (pintype "bidirectional"))
      (node (ref "USB1") (pin "GND2") (pinfunction "GND_GND2") (pintype "bidirectional"))
      (node (ref "USB1") (pin "GND3") (pinfunction "GND_GND3") (pintype "bidirectional"))
      (node (ref "USB1") (pin "GND4") (pinfunction "GND_GND4") (pintype "bidirectional"))
      (node (ref "USB2") (pin "5") (pinfunction "GND_5") (pintype "bidirectional"))
      (node (ref "USB2") (pin "GND1") (pinfunction "GND_GND1") (pintype "bidirectional"))
      (node (ref "USB2") (pin "GND2") (pinfunction "GND_GND2") (pintype "bidirectional"))
      (node (ref "USB2") (pin "GND3") (pinfunction "GND_GND3") (pintype "bidirectional"))
      (node (ref "USB2") (pin "GND4") (pinfunction "GND_GND4") (pintype "bidirectional"))
      (node (ref "X1") (pin "2") (pinfunction "CASE_2") (pintype "passive"))
      (node (ref "X1") (pin "4") (pinfunction "CASE_4") (pintype "passive"))
      (node (ref "X3") (pin "GND-1") (pinfunction "CASE_GND-1") (pintype "passive"))
      (node (ref "X3") (pin "GND-2") (pinfunction "CASE_GND-2") (pintype "passive"))
    )
    (net (code "55") (name "GREEN_BOT") (class "Default")
      (node (ref "GREEN_BOT") (pin "2") (pinfunction "P$2_2") (pintype "bidirectional"))
      (node (ref "U7") (pin "136") (pinfunction "PC25_136") (pintype "bidirectional"))
    )
    (net (code "56") (name "GREEN_TOP") (class "Default")
      (node (ref "GREEN_TOP") (pin "2") (pinfunction "P$2_2") (pintype "bidirectional"))
      (node (ref "U7") (pin "133") (pinfunction "PC22_133") (pintype "bidirectional"))
    )
    (net (code "57") (name "IN_L") (class "Default")
      (node (ref "C38") (pin "1") (pinfunction "1_1") (pintype "passive"))
      (node (ref "LINE_IN") (pin "4") (pinfunction "L_4") (pintype "bidirectional"))
      (node (ref "R23") (pin "2") (pinfunction "2_2") (pintype "passive"))
    )
    (net (code "58") (name "IN_R") (class "Default")
      (node (ref "C37") (pin "1") (pinfunction "1_1") (pintype "passive"))
      (node (ref "LINE_IN") (pin "1") (pinfunction "R_1") (pintype "bidirectional"))
    )
    (net (code "59") (name "LINEIN_SENSE") (class "Default")
      (node (ref "LINEIN_SENSE") (pin "2") (pinfunction "P$2_2") (pintype "bidirectional"))
      (node (ref "U7") (pin "101") (pinfunction "PC19_101") (pintype "bidirectional"))
    )
    (net (code "60") (name "LINE_L") (class "Default")
      (node (ref "LINE_L") (pin "1") (pinfunction "P$1_1") (pintype "bidirectional"))
      (node (ref "U3") (pin "22") (pinfunction "LOL_22") (pintype "bidirectional"))
    )
    (net (code "61") (name "LINE_R") (class "Default")
      (node (ref "LINE_R") (pin "1") (pinfunction "P$1_1") (pintype "bidirectional"))
      (node (ref "U3") (pin "23") (pinfunction "LOR_23") (pintype "bidirectional"))
    )
    (net (code "62") (name "LNA_EN") (class "Default")
      (node (ref "U1") (pin "38") (pinfunction "XLNAEN_38") (pintype "bidirectional"))
      (node (ref "U2") (pin "6") (pinfunction "EN_6") (pintype "bidirectional"))
    )
    (net (code "63") (name "MCLK") (class "Default")
      (node (ref "CC8531_MCLK") (pin "2") (pinfunction "P$2_2") (pintype "bidirectional"))
      (node (ref "U3") (pin "1") (pinfunction "MCLK_1") (pintype "bidirectional"))
    )
    (net (code "64") (name "MISO") (class "Default")
      (node (ref "AUX_MISO") (pin "2") (pinfunction "P$2_2") (pintype "bidirectional"))
      (node (ref "CC8531_MISO") (pin "2") (pinfunction "P$2_2") (pintype "bidirectional"))
      (node (ref "CODEC_MISO") (pin "2") (pinfunction "P$2_2") (pintype "bidirectional"))
      (node (ref "SD_MISO") (pin "1") (pinfunction "P$1_1") (pintype "bidirectional"))
      (node (ref "U7") (pin "108") (pinfunction "PA25_108") (pintype "bidirectional"))
    )
    (net (code "65") (name "MOSI") (class "Default")
      (node (ref "AUX_MOSI") (pin "2") (pinfunction "P$2_2") (pintype "bidirectional"))
      (node (ref "CC8531_MOSI") (pin "2") (pinfunction "P$2_2") (pintype "bidirectional"))
      (node (ref "CODEC_MOSI") (pin "2") (pinfunction "P$2_2") (pintype "bidirectional"))
      (node (ref "SD_MOSI") (pin "1") (pinfunction "P$1_1") (pintype "bidirectional"))
      (node (ref "U7") (pin "109") (pinfunction "PA26_109") (pintype "bidirectional"))
    )
    (net (code "66") (name "M_BCLK") (class "Default")
      (node (ref "BCLK") (pin "2") (pinfunction "P$2_2") (pintype "bidirectional"))
      (node (ref "U7") (pin "7") (pinfunction "PA14_7") (pintype "bidirectional"))
    )
    (net (code "67") (name "M_DIN{slash}S_DOUT") (class "Default")
      (node (ref "DOUT") (pin "2") (pinfunction "P$2_2") (pintype "bidirectional"))
      (node (ref "U7") (pin "89") (pinfunction "PB18_89") (pintype "bidirectional"))
    )
    (net (code "68") (name "M_DOUT{slash}S_DIN") (class "Default")
      (node (ref "DIN") (pin "2") (pinfunction "P$2_2") (pintype "bidirectional"))
      (node (ref "U7") (pin "78") (pinfunction "PA16_78") (pintype "bidirectional"))
    )
    (net (code "69") (name "M_WCLK") (class "Default")
      (node (ref "U7") (pin "8") (pinfunction "PA15_8") (pintype "bidirectional"))
      (node (ref "WCLK") (pin "2") (pinfunction "P$2_2") (pintype "bidirectional"))
    )
    (net (code "70") (name "Net-(!SD_CARD-P$2)") (class "Default")
      (node (ref "!SD_CARD") (pin "2") (pinfunction "P$2_2") (pintype "bidirectional"))
      (node (ref "MICROSD1") (pin "SWA") (pinfunction "SWA_SWA") (pintype "bidirectional"))
    )
    (net (code "71") (name "Net-(AMP_AVDD-P$1)") (class "Default")
      (node (ref "AMP_AVDD") (pin "1") (pinfunction "P$1_1") (pintype "bidirectional"))
      (node (ref "L3") (pin "2") (pinfunction "2_2") (pintype "passive"))
    )
    (net (code "72") (name "Net-(AUX_VDD-P$1)") (class "Default")
      (node (ref "AUX_VDD") (pin "1") (pinfunction "P$1_1") (pintype "bidirectional"))
      (node (ref "L18") (pin "2") (pinfunction "2_2") (pintype "passive"))
    )
    (net (code "73") (name "Net-(AVR-PadA)") (class "Default")
      (node (ref "AVR") (pin "A") (pinfunction "A_A") (pintype "passive"))
      (node (ref "R44") (pin "1") (pinfunction "1_1") (pintype "passive"))
    )
    (net (code "74") (name "Net-(AVR1-PadA)") (class "Default")
      (node (ref "AVR1") (pin "A") (pinfunction "A_A") (pintype "passive"))
      (node (ref "R6") (pin "1") (pinfunction "1_1") (pintype "passive"))
    )
    (net (code "75") (name "Net-(AVR2-PadA)") (class "Default")
      (node (ref "AVR2") (pin "A") (pinfunction "A_A") (pintype "passive"))
      (node (ref "R47") (pin "1") (pinfunction "1_1") (pintype "passive"))
    )
    (net (code "76") (name "Net-(AVR_VDD-P$1)") (class "Default")
      (node (ref "AVR_VDD") (pin "1") (pinfunction "P$1_1") (pintype "bidirectional"))
      (node (ref "L16") (pin "2") (pinfunction "2_2") (pintype "passive"))
    )
    (net (code "77") (name "Net-(BATTERY-P)") (class "Default")
      (node (ref "BATTERY") (pin "+") (pinfunction "P_+") (pintype "passive"))
      (node (ref "Q1") (pin "2") (pinfunction "S_2") (pintype "passive"))
      (node (ref "U6") (pin "9") (pinfunction "BAT_9") (pintype "bidirectional"))
    )
    (net (code "78") (name "Net-(C25-Pad1)") (class "Default")
      (node (ref "C25") (pin "1") (pinfunction "1_1") (pintype "passive"))
      (node (ref "L8") (pin "2") (pinfunction "2_2") (pintype "passive"))
    )
    (net (code "79") (name "Net-(C25-Pad2)") (class "Default")
      (node (ref "C25") (pin "2") (pinfunction "2_2") (pintype "passive"))
      (node (ref "C26") (pin "1") (pinfunction "1_1") (pintype "passive"))
      (node (ref "C28") (pin "1") (pinfunction "1_1") (pintype "passive"))
      (node (ref "L10") (pin "2") (pinfunction "2_2") (pintype "passive"))
    )
    (net (code "80") (name "Net-(C26-Pad2)") (class "Default")
      (node (ref "C26") (pin "2") (pinfunction "2_2") (pintype "passive"))
      (node (ref "SMA") (pin "SIG") (pinfunction "SIG_SIG") (pintype "bidirectional"))
    )
    (net (code "81") (name "Net-(C27-Pad1)") (class "Default")
      (node (ref "C27") (pin "1") (pinfunction "1_1") (pintype "passive"))
      (node (ref "L7") (pin "2") (pinfunction "2_2") (pintype "passive"))
      (node (ref "L8") (pin "1") (pinfunction "1_1") (pintype "passive"))
    )
    (net (code "82") (name "Net-(C54-Pad1)") (class "Default")
      (node (ref "C54") (pin "1") (pinfunction "1_1") (pintype "passive"))
      (node (ref "R19") (pin "1") (pinfunction "1_1") (pintype "passive"))
    )
    (net (code "83") (name "Net-(C70-Pad2)") (class "Default")
      (node (ref "C70") (pin "2") (pinfunction "2_2") (pintype "passive"))
      (node (ref "R16") (pin "2") (pinfunction "2_2") (pintype "passive"))
    )
    (net (code "84") (name "Net-(C71-Pad2)") (class "Default")
      (node (ref "C71") (pin "2") (pinfunction "2_2") (pintype "passive"))
      (node (ref "R13") (pin "2") (pinfunction "2_2") (pintype "passive"))
    )
    (net (code "85") (name "Net-(CC8531-PadC)") (class "Default")
      (node (ref "CC8531") (pin "C") (pinfunction "C_C") (pintype "passive"))
      (node (ref "R5") (pin "2") (pinfunction "2_2") (pintype "passive"))
    )
    (net (code "86") (name "Net-(CC8531_AVDD-P$1)") (class "Default")
      (node (ref "CC8531_AVDD") (pin "1") (pinfunction "P$1_1") (pintype "bidirectional"))
      (node (ref "L2") (pin "2") (pinfunction "2_2") (pintype "passive"))
    )
    (net (code "87") (name "Net-(CC8531_IOVDD-P$1)") (class "Default")
      (node (ref "CC8531_IOVDD") (pin "1") (pinfunction "P$1_1") (pintype "bidirectional"))
      (node (ref "L1") (pin "2") (pinfunction "2_2") (pintype "passive"))
    )
    (net (code "88") (name "Net-(CHARGE-PadA)") (class "Default")
      (node (ref "CHARGE") (pin "A") (pinfunction "A_A") (pintype "passive"))
      (node (ref "R18") (pin "1") (pinfunction "1_1") (pintype "passive"))
    )
    (net (code "89") (name "Net-(CODEC_AVDD-P$1)") (class "Default")
      (node (ref "CODEC_AVDD") (pin "1") (pinfunction "P$1_1") (pintype "bidirectional"))
      (node (ref "L14") (pin "2") (pinfunction "2_2") (pintype "passive"))
    )
    (net (code "90") (name "Net-(CODEC_DVDD-P$1)") (class "Default")
      (node (ref "CODEC_DVDD") (pin "1") (pinfunction "P$1_1") (pintype "bidirectional"))
      (node (ref "L15") (pin "2") (pinfunction "2_2") (pintype "passive"))
    )
    (net (code "91") (name "Net-(EXT-P$2)") (class "Default")
      (node (ref "CC_DEBUG") (pin "9") (pinfunction "9_9") (pintype "bidirectional"))
      (node (ref "EXT") (pin "2") (pinfunction "P$2_2") (pintype "bidirectional"))
    )
    (net (code "92") (name "Net-(LINE_L-P$2)") (class "Default")
      (node (ref "C71") (pin "1") (pinfunction "1_1") (pintype "passive"))
      (node (ref "LINE_L") (pin "2") (pinfunction "P$2_2") (pintype "bidirectional"))
      (node (ref "PHONE_L") (pin "2") (pinfunction "P$2_2") (pintype "bidirectional"))
    )
    (net (code "93") (name "Net-(LINE_R-P$2)") (class "Default")
      (node (ref "C70") (pin "1") (pinfunction "1_1") (pintype "passive"))
      (node (ref "LINE_R") (pin "2") (pinfunction "P$2_2") (pintype "bidirectional"))
      (node (ref "PHONE_R") (pin "2") (pinfunction "P$2_2") (pintype "bidirectional"))
    )
    (net (code "94") (name "Net-(MICROSD1-MISO)") (class "Default")
      (node (ref "MICROSD1") (pin "DAT0") (pinfunction "MISO_DAT0") (pintype "bidirectional"))
      (node (ref "SD_MISO") (pin "2") (pinfunction "P$2_2") (pintype "bidirectional"))
    )
    (net (code "95") (name "Net-(MICROSD1-MOSI)") (class "Default")
      (node (ref "MICROSD1") (pin "CMD") (pinfunction "MOSI_CMD") (pintype "bidirectional"))
      (node (ref "SD_MOSI") (pin "2") (pinfunction "P$2_2") (pintype "bidirectional"))
    )
    (net (code "96") (name "Net-(MICROSD1-SCLK)") (class "Default")
      (node (ref "MICROSD1") (pin "CLK") (pinfunction "SCLK_CLK") (pintype "bidirectional"))
      (node (ref "SD_SCLK") (pin "2") (pinfunction "P$2_2") (pintype "bidirectional"))
    )
    (net (code "97") (name "Net-(MICROSD1-~{CS})") (class "Default")
      (node (ref "MICROSD1") (pin "CD/DAT3") (pinfunction "~{CS}_CD/DAT3") (pintype "bidirectional"))
      (node (ref "SD_CS") (pin "2") (pinfunction "P$2_2") (pintype "bidirectional"))
    )
    (net (code "98") (name "Net-(POWER-PadA)") (class "Default")
      (node (ref "POWER") (pin "A") (pinfunction "A_A") (pintype "passive"))
      (node (ref "R3") (pin "1") (pinfunction "1_1") (pintype "passive"))
    )
    (net (code "99") (name "Net-(Q1-D)") (class "Default")
      (node (ref "C52") (pin "1") (pinfunction "1_1") (pintype "passive"))
      (node (ref "F1") (pin "1") (pinfunction "1_1") (pintype "passive"))
      (node (ref "L17") (pin "2") (pinfunction "2_2") (pintype "passive"))
      (node (ref "Q1") (pin "3") (pinfunction "D_3") (pintype "passive"))
      (node (ref "U6") (pin "10") (pinfunction "VOUT_10") (pintype "bidirectional"))
      (node (ref "U6") (pin "3") (pinfunction "VOUTS_3") (pintype "bidirectional"))
    )
    (net (code "100") (name "Net-(Q1-G)") (class "Default")
      (node (ref "Q1") (pin "1") (pinfunction "G_1") (pintype "passive"))
      (node (ref "U6") (pin "8") (pinfunction "GATE_8") (pintype "bidirectional"))
    )
    (net (code "101") (name "Net-(Q2-D)") (class "Default")
      (node (ref "LED_UL") (pin "1") (pinfunction "KR_1") (pintype "passive"))
      (node (ref "LED_UL") (pin "1-2") (pinfunction "KR_1-2") (pintype "passive"))
      (node (ref "LED_UR") (pin "1") (pinfunction "KR_1") (pintype "passive"))
      (node (ref "LED_UR") (pin "1-2") (pinfunction "KR_1-2") (pintype "passive"))
      (node (ref "Q2") (pin "3") (pinfunction "D_3") (pintype "passive"))
    )
    (net (code "102") (name "Net-(Q3-D)") (class "Default")
      (node (ref "LED_UL") (pin "4") (pinfunction "KG_4") (pintype "passive"))
      (node (ref "LED_UL") (pin "4-2") (pinfunction "KG_4-2") (pintype "passive"))
      (node (ref "LED_UR") (pin "4") (pinfunction "KG_4") (pintype "passive"))
      (node (ref "LED_UR") (pin "4-2") (pinfunction "KG_4-2") (pintype "passive"))
      (node (ref "Q3") (pin "3") (pinfunction "D_3") (pintype "passive"))
    )
    (net (code "103") (name "Net-(Q4-D)") (class "Default")
      (node (ref "LED_UL") (pin "3") (pinfunction "KB_3") (pintype "passive"))
      (node (ref "LED_UL") (pin "3-2") (pinfunction "KB_3-2") (pintype "passive"))
      (node (ref "LED_UR") (pin "3") (pinfunction "KB_3") (pintype "passive"))
      (node (ref "LED_UR") (pin "3-2") (pinfunction "KB_3-2") (pintype "passive"))
      (node (ref "Q4") (pin "3") (pinfunction "D_3") (pintype "passive"))
    )
    (net (code "104") (name "Net-(Q5-D)") (class "Default")
      (node (ref "LED_LL") (pin "1") (pinfunction "KR_1") (pintype "passive"))
      (node (ref "LED_LL") (pin "1-2") (pinfunction "KR_1-2") (pintype "passive"))
      (node (ref "LED_LR") (pin "1") (pinfunction "KR_1") (pintype "passive"))
      (node (ref "LED_LR") (pin "1-2") (pinfunction "KR_1-2") (pintype "passive"))
      (node (ref "Q5") (pin "3") (pinfunction "D_3") (pintype "passive"))
    )
    (net (code "105") (name "Net-(Q6-D)") (class "Default")
      (node (ref "LED_LL") (pin "4") (pinfunction "KG_4") (pintype "passive"))
      (node (ref "LED_LL") (pin "4-2") (pinfunction "KG_4-2") (pintype "passive"))
      (node (ref "LED_LR") (pin "4") (pinfunction "KG_4") (pintype "passive"))
      (node (ref "LED_LR") (pin "4-2") (pinfunction "KG_4-2") (pintype "passive"))
      (node (ref "Q6") (pin "3") (pinfunction "D_3") (pintype "passive"))
    )
    (net (code "106") (name "Net-(Q7-D)") (class "Default")
      (node (ref "LED_LL") (pin "3") (pinfunction "KB_3") (pintype "passive"))
      (node (ref "LED_LL") (pin "3-2") (pinfunction "KB_3-2") (pintype "passive"))
      (node (ref "LED_LR") (pin "3") (pinfunction "KB_3") (pintype "passive"))
      (node (ref "LED_LR") (pin "3-2") (pinfunction "KB_3-2") (pintype "passive"))
      (node (ref "Q7") (pin "3") (pinfunction "D_3") (pintype "passive"))
    )
    (net (code "107") (name "Net-(R26-Pad2)") (class "Default")
      (node (ref "R26") (pin "2") (pinfunction "2_2") (pintype "passive"))
      (node (ref "SW1") (pin "P$1") (pinfunction "P$1_P$1") (pintype "bidirectional"))
    )
    (net (code "108") (name "Net-(R33-Pad2)") (class "Default")
      (node (ref "R33") (pin "2") (pinfunction "2_2") (pintype "passive"))
      (node (ref "SW4") (pin "P$1") (pinfunction "P$1_P$1") (pintype "bidirectional"))
    )
    (net (code "109") (name "Net-(R34-Pad2)") (class "Default")
      (node (ref "R34") (pin "2") (pinfunction "2_2") (pintype "passive"))
      (node (ref "SW5") (pin "P$1") (pinfunction "P$1_P$1") (pintype "bidirectional"))
    )
    (net (code "110") (name "Net-(R35-Pad2)") (class "Default")
      (node (ref "R35") (pin "2") (pinfunction "2_2") (pintype "passive"))
      (node (ref "SW6") (pin "P$1") (pinfunction "P$1_P$1") (pintype "bidirectional"))
    )
    (net (code "111") (name "Net-(R37-Pad2)") (class "Default")
      (node (ref "R37") (pin "2") (pinfunction "2_2") (pintype "passive"))
      (node (ref "SW7") (pin "P$1") (pinfunction "P$1_P$1") (pintype "bidirectional"))
    )
    (net (code "112") (name "Net-(R38-Pad2)") (class "Default")
      (node (ref "R38") (pin "2") (pinfunction "2_2") (pintype "passive"))
      (node (ref "SW8") (pin "P$1") (pinfunction "P$1_P$1") (pintype "bidirectional"))
    )
    (net (code "113") (name "Net-(R39-Pad2)") (class "Default")
      (node (ref "R39") (pin "2") (pinfunction "2_2") (pintype "passive"))
      (node (ref "SW9") (pin "P$1") (pinfunction "P$1_P$1") (pintype "bidirectional"))
    )
    (net (code "114") (name "Net-(R40-Pad2)") (class "Default")
      (node (ref "R40") (pin "2") (pinfunction "2_2") (pintype "passive"))
      (node (ref "SW10") (pin "P$1") (pinfunction "P$1_P$1") (pintype "bidirectional"))
    )
    (net (code "115") (name "Net-(SD_VDD-P$1)") (class "Default")
      (node (ref "MICROSD1") (pin "VDD") (pinfunction "VDD_VDD") (pintype "bidirectional"))
      (node (ref "SD_VDD") (pin "1") (pinfunction "P$1_1") (pintype "bidirectional"))
    )
    (net (code "116") (name "Net-(U1-AD0{slash}GIO7)") (class "Default")
      (node (ref "L11") (pin "2") (pinfunction "2_2") (pintype "passive"))
      (node (ref "U1") (pin "16") (pinfunction "AD0/GIO7_16") (pintype "bidirectional"))
    )
    (net (code "117") (name "Net-(U1-AD1{slash}GIO8)") (class "Default")
      (node (ref "L13") (pin "2") (pinfunction "2_2") (pintype "passive"))
      (node (ref "U1") (pin "17") (pinfunction "AD1/GIO8_17") (pintype "bidirectional"))
    )
    (net (code "118") (name "Net-(U1-BCLK{slash}GIO5)") (class "Default")
      (node (ref "L6") (pin "2") (pinfunction "2_2") (pintype "passive"))
      (node (ref "U1") (pin "14") (pinfunction "BCLK/GIO5_14") (pintype "bidirectional"))
    )
    (net (code "119") (name "Net-(U1-DCPL)") (class "Default")
      (node (ref "C23") (pin "1") (pinfunction "1_1") (pintype "passive"))
      (node (ref "U1") (pin "39") (pinfunction "DCPL_39") (pintype "bidirectional"))
    )
    (net (code "120") (name "Net-(U1-GIO3)") (class "Default")
      (node (ref "R5") (pin "1") (pinfunction "1_1") (pintype "passive"))
      (node (ref "U1") (pin "9") (pinfunction "GIO3_9") (pintype "bidirectional"))
    )
    (net (code "121") (name "Net-(U1-MCLK{slash}GIO4)") (class "Default")
      (node (ref "L5") (pin "2") (pinfunction "2_2") (pintype "passive"))
      (node (ref "U1") (pin "13") (pinfunction "MCLK/GIO4_13") (pintype "bidirectional"))
    )
    (net (code "122") (name "Net-(U1-RBIAS)") (class "Default")
      (node (ref "R4") (pin "2") (pinfunction "2_2") (pintype "passive"))
      (node (ref "U1") (pin "30") (pinfunction "RBIAS_30") (pintype "bidirectional"))
    )
    (net (code "123") (name "Net-(U1-RSTN)") (class "Default")
      (node (ref "L4") (pin "1") (pinfunction "1_1") (pintype "passive"))
      (node (ref "U1") (pin "11") (pinfunction "RSTN_11") (pintype "bidirectional"))
    )
    (net (code "124") (name "Net-(U1-USBN)") (class "Default")
      (node (ref "C14") (pin "1") (pinfunction "1_1") (pintype "passive"))
      (node (ref "R1") (pin "1") (pinfunction "1_1") (pintype "passive"))
      (node (ref "U1") (pin "1") (pinfunction "USBN_1") (pintype "bidirectional"))
    )
    (net (code "125") (name "Net-(U1-USBP)") (class "Default")
      (node (ref "C13") (pin "1") (pinfunction "1_1") (pintype "passive"))
      (node (ref "R2") (pin "1") (pinfunction "1_1") (pintype "passive"))
      (node (ref "U1") (pin "2") (pinfunction "USBP_2") (pintype "bidirectional"))
    )
    (net (code "126") (name "Net-(U1-WCLK{slash}GIO6)") (class "Default")
      (node (ref "L9") (pin "2") (pinfunction "2_2") (pintype "passive"))
      (node (ref "U1") (pin "15") (pinfunction "WCLK/GIO6_15") (pintype "bidirectional"))
    )
    (net (code "127") (name "Net-(U1-X0)") (class "Default")
      (node (ref "C24") (pin "1") (pinfunction "1_1") (pintype "passive"))
      (node (ref "U1") (pin "22") (pinfunction "X0_22") (pintype "bidirectional"))
      (node (ref "X1") (pin "3") (pinfunction "2_3") (pintype "passive"))
    )
    (net (code "128") (name "Net-(U1-X1)") (class "Default")
      (node (ref "C29") (pin "1") (pinfunction "1_1") (pintype "passive"))
      (node (ref "U1") (pin "21") (pinfunction "X1_21") (pintype "bidirectional"))
      (node (ref "X1") (pin "1") (pinfunction "1_1") (pintype "passive"))
    )
    (net (code "129") (name "Net-(U1-XPAEN)") (class "Default")
      (node (ref "L12") (pin "1") (pinfunction "1_1") (pintype "passive"))
      (node (ref "U1") (pin "36") (pinfunction "XPAEN_36") (pintype "bidirectional"))
    )
    (net (code "130") (name "Net-(U2-ANT)") (class "Default")
      (node (ref "L7") (pin "1") (pinfunction "1_1") (pintype "passive"))
      (node (ref "U2") (pin "11") (pinfunction "ANT_11") (pintype "bidirectional"))
    )
    (net (code "131") (name "Net-(U2-BIAS)") (class "Default")
      (node (ref "R8") (pin "2") (pinfunction "2_2") (pintype "passive"))
      (node (ref "U2") (pin "15") (pinfunction "BIAS_15") (pintype "bidirectional"))
    )
    (net (code "132") (name "Net-(U2-HGM)") (class "Default")
      (node (ref "R9") (pin "1") (pinfunction "1_1") (pintype "passive"))
      (node (ref "U2") (pin "7") (pinfunction "HGM_7") (pintype "bidirectional"))
    )
    (net (code "133") (name "Net-(U3-AVDD)") (class "Default")
      (node (ref "C48") (pin "1") (pinfunction "1_1") (pintype "passive"))
      (node (ref "U3") (pin "24") (pinfunction "AVDD_24") (pintype "bidirectional"))
    )
    (net (code "134") (name "Net-(U3-DVDD)") (class "Default")
      (node (ref "C49") (pin "1") (pinfunction "1_1") (pintype "passive"))
      (node (ref "U3") (pin "29") (pinfunction "DVDD_29") (pintype "bidirectional"))
    )
    (net (code "135") (name "Net-(U3-IN1_L)") (class "Default")
      (node (ref "C38") (pin "2") (pinfunction "2_2") (pintype "passive"))
      (node (ref "U3") (pin "13") (pinfunction "IN1_L_13") (pintype "bidirectional"))
    )
    (net (code "136") (name "Net-(U3-IN1_R)") (class "Default")
      (node (ref "C37") (pin "2") (pinfunction "2_2") (pintype "passive"))
      (node (ref "U3") (pin "14") (pinfunction "IN1_R_14") (pintype "bidirectional"))
    )
    (net (code "137") (name "Net-(U3-REF)") (class "Default")
      (node (ref "C50") (pin "1") (pinfunction "1_1") (pintype "passive"))
      (node (ref "U3") (pin "18") (pinfunction "REF_18") (pintype "bidirectional"))
    )
    (net (code "138") (name "Net-(U5-VIN)") (class "Default")
      (node (ref "F1") (pin "2") (pinfunction "2_2") (pintype "passive"))
      (node (ref "U5") (pin "1") (pinfunction "VIN_1") (pintype "bidirectional"))
    )
    (net (code "139") (name "Net-(U6-CLRPROG)") (class "Default")
      (node (ref "R19") (pin "2") (pinfunction "2_2") (pintype "passive"))
      (node (ref "R20") (pin "2") (pinfunction "2_2") (pintype "passive"))
      (node (ref "U6") (pin "2") (pinfunction "CLRPROG_2") (pintype "bidirectional"))
    )
    (net (code "140") (name "Net-(U6-C{slash}X)") (class "Default")
      (node (ref "R21") (pin "2") (pinfunction "2_2") (pintype "passive"))
      (node (ref "U6") (pin "5") (pinfunction "C/X_5") (pintype "bidirectional"))
      (node (ref "U6") (pin "6") (pinfunction "PROG_6") (pintype "bidirectional"))
    )
    (net (code "141") (name "Net-(U6-SW)") (class "Default")
      (node (ref "L17") (pin "1") (pinfunction "1_1") (pintype "passive"))
      (node (ref "U6") (pin "12") (pinfunction "SW_12") (pintype "bidirectional"))
    )
    (net (code "142") (name "Net-(U6-~{CHRG})") (class "Default")
      (node (ref "CHARGE") (pin "C") (pinfunction "C_C") (pintype "passive"))
      (node (ref "U6") (pin "7") (pinfunction "~{CHRG}_7") (pintype "bidirectional"))
    )
    (net (code "143") (name "Net-(U7F-DFSDM)") (class "Default")
      (node (ref "R41") (pin "1") (pinfunction "1_1") (pintype "passive"))
      (node (ref "U7") (pin "43") (pinfunction "DFSDM_43") (pintype "bidirectional"))
    )
    (net (code "144") (name "Net-(U7F-DFSDP)") (class "Default")
      (node (ref "R42") (pin "1") (pinfunction "1_1") (pintype "passive"))
      (node (ref "U7") (pin "42") (pinfunction "DFSDP_42") (pintype "bidirectional"))
    )
    (net (code "145") (name "Net-(U7F-FWUP)") (class "Default")
      (node (ref "R43") (pin "2") (pinfunction "2_2") (pintype "passive"))
      (node (ref "U7") (pin "53") (pinfunction "FWUP_53") (pintype "bidirectional"))
    )
    (net (code "146") (name "Net-(U7F-VBG)") (class "Default")
      (node (ref "C68") (pin "1") (pinfunction "1_1") (pintype "passive"))
      (node (ref "R32") (pin "2") (pinfunction "2_2") (pintype "passive"))
      (node (ref "U7") (pin "40") (pinfunction "VBG_40") (pintype "bidirectional"))
    )
    (net (code "147") (name "Net-(U7F-XIN)") (class "Default")
      (node (ref "C30") (pin "1") (pinfunction "1_1") (pintype "passive"))
      (node (ref "U7") (pin "36") (pinfunction "XIN_36") (pintype "bidirectional"))
      (node (ref "X3") (pin "X2") (pinfunction "2_X2") (pintype "passive"))
    )
    (net (code "148") (name "Net-(U7F-XOUT)") (class "Default")
      (node (ref "C56") (pin "1") (pinfunction "1_1") (pintype "passive"))
      (node (ref "U7") (pin "35") (pinfunction "XOUT_35") (pintype "bidirectional"))
      (node (ref "X3") (pin "X1") (pinfunction "1_X1") (pintype "passive"))
    )
    (net (code "149") (name "Net-(U8-SNS3)") (class "Default")
      (node (ref "C58") (pin "1") (pinfunction "1_1") (pintype "passive"))
      (node (ref "U8") (pin "8") (pinfunction "SNS3_8") (pintype "bidirectional"))
    )
    (net (code "150") (name "Net-(U8-SNS3K)") (class "Default")
      (node (ref "C58") (pin "2") (pinfunction "2_2") (pintype "passive"))
      (node (ref "R33") (pin "1") (pinfunction "1_1") (pintype "passive"))
      (node (ref "U8") (pin "9") (pinfunction "SNS3K_9") (pintype "bidirectional"))
    )
    (net (code "151") (name "Net-(U8-SNS4)") (class "Default")
      (node (ref "C59") (pin "1") (pinfunction "1_1") (pintype "passive"))
      (node (ref "U8") (pin "10") (pinfunction "SNS4_10") (pintype "bidirectional"))
    )
    (net (code "152") (name "Net-(U8-SNS4K)") (class "Default")
      (node (ref "C59") (pin "2") (pinfunction "2_2") (pintype "passive"))
      (node (ref "R34") (pin "1") (pinfunction "1_1") (pintype "passive"))
      (node (ref "U8") (pin "11") (pinfunction "SNS4K_11") (pintype "bidirectional"))
    )
    (net (code "153") (name "Net-(U8-SNS5)") (class "Default")
      (node (ref "C60") (pin "1") (pinfunction "1_1") (pintype "passive"))
      (node (ref "U8") (pin "12") (pinfunction "SNS5_12") (pintype "bidirectional"))
    )
    (net (code "154") (name "Net-(U8-SNS5K)") (class "Default")
      (node (ref "C60") (pin "2") (pinfunction "2_2") (pintype "passive"))
      (node (ref "R35") (pin "1") (pinfunction "1_1") (pintype "passive"))
      (node (ref "U8") (pin "13") (pinfunction "SNS5K_13") (pintype "bidirectional"))
    )
    (net (code "155") (name "Net-(U8-SNS6)") (class "Default")
      (node (ref "C61") (pin "1") (pinfunction "1_1") (pintype "passive"))
      (node (ref "U8") (pin "20") (pinfunction "SNS6_20") (pintype "bidirectional"))
    )
    (net (code "156") (name "Net-(U8-SNS6K)") (class "Default")
      (node (ref "C61") (pin "2") (pinfunction "2_2") (pintype "passive"))
      (node (ref "R37") (pin "1") (pinfunction "1_1") (pintype "passive"))
      (node (ref "U8") (pin "19") (pinfunction "SNS6K_19") (pintype "bidirectional"))
    )
    (net (code "157") (name "Net-(U8-SNS7K{slash}DETECT0)") (class "Default")
      (node (ref "C62") (pin "2") (pinfunction "2_2") (pintype "passive"))
      (node (ref "R38") (pin "1") (pinfunction "1_1") (pintype "passive"))
      (node (ref "U8") (pin "22") (pinfunction "SNS7K/DETECT0_22") (pintype "bidirectional"))
    )
    (net (code "158") (name "Net-(U8-SNS7{slash}DETECT1)") (class "Default")
      (node (ref "C62") (pin "1") (pinfunction "1_1") (pintype "passive"))
      (node (ref "U8") (pin "23") (pinfunction "SNS7/DETECT1_23") (pintype "bidirectional"))
    )
    (net (code "159") (name "Net-(U8-SNS8K{slash}DETECT3)") (class "Default")
      (node (ref "C66") (pin "2") (pinfunction "2_2") (pintype "passive"))
      (node (ref "R39") (pin "1") (pinfunction "1_1") (pintype "passive"))
      (node (ref "U8") (pin "25") (pinfunction "SNS8K/DETECT3_25") (pintype "bidirectional"))
    )
    (net (code "160") (name "Net-(U8-SNS8{slash}DETECT2)") (class "Default")
      (node (ref "C66") (pin "1") (pinfunction "1_1") (pintype "passive"))
      (node (ref "U8") (pin "24") (pinfunction "SNS8/DETECT2_24") (pintype "bidirectional"))
    )
    (net (code "161") (name "Net-(U8-SNS9K{slash}DETECT5)") (class "Default")
      (node (ref "C67") (pin "2") (pinfunction "2_2") (pintype "passive"))
      (node (ref "R40") (pin "1") (pinfunction "1_1") (pintype "passive"))
      (node (ref "U8") (pin "27") (pinfunction "SNS9K/DETECT5_27") (pintype "bidirectional"))
    )
    (net (code "162") (name "Net-(U8-SNS9{slash}DETECT4)") (class "Default")
      (node (ref "C67") (pin "1") (pinfunction "1_1") (pintype "passive"))
      (node (ref "U8") (pin "26") (pinfunction "SNS9/DETECT4_26") (pintype "bidirectional"))
    )
    (net (code "163") (name "Net-(U8-SNS10K{slash}SYNC)") (class "Default")
      (node (ref "C55") (pin "2") (pinfunction "2_2") (pintype "passive"))
      (node (ref "R26") (pin "1") (pinfunction "1_1") (pintype "passive"))
      (node (ref "U8") (pin "31") (pinfunction "SNS10K/SYNC_31") (pintype "bidirectional"))
    )
    (net (code "164") (name "Net-(U8-SNS10{slash}DETECT16)") (class "Default")
      (node (ref "C55") (pin "1") (pinfunction "1_1") (pintype "passive"))
      (node (ref "U8") (pin "30") (pinfunction "SNS10/DETECT16_30") (pintype "bidirectional"))
    )
    (net (code "165") (name "Net-(U8-~{RESET})") (class "Default")
      (node (ref "R36") (pin "1") (pinfunction "1_1") (pintype "passive"))
      (node (ref "U8") (pin "29") (pinfunction "~{RESET}_29") (pintype "bidirectional"))
    )
    (net (code "166") (name "Net-(U9-BYPASS)") (class "Default")
      (node (ref "C33") (pin "1") (pinfunction "1_1") (pintype "passive"))
      (node (ref "U9") (pin "1") (pinfunction "BYPASS_1") (pintype "bidirectional"))
    )
    (net (code "167") (name "Net-(U9-INA)") (class "Default")
      (node (ref "R12") (pin "2") (pinfunction "2_2") (pintype "passive"))
      (node (ref "R13") (pin "1") (pinfunction "1_1") (pintype "passive"))
      (node (ref "U9") (pin "8") (pinfunction "INA_8") (pintype "bidirectional"))
    )
    (net (code "168") (name "Net-(U9-INB)") (class "Default")
      (node (ref "R15") (pin "2") (pinfunction "2_2") (pintype "passive"))
      (node (ref "R16") (pin "1") (pinfunction "1_1") (pintype "passive"))
      (node (ref "U9") (pin "4") (pinfunction "INB_4") (pintype "bidirectional"))
    )
    (net (code "169") (name "Net-(U9-OUTB)") (class "Default")
      (node (ref "C39") (pin "1") (pinfunction "1_1") (pintype "passive"))
      (node (ref "R15") (pin "1") (pinfunction "1_1") (pintype "passive"))
      (node (ref "U9") (pin "5") (pinfunction "OUTB_5") (pintype "bidirectional"))
    )
    (net (code "170") (name "Net-(U9-SHUTDOWN)") (class "Default")
      (node (ref "R31") (pin "1") (pinfunction "1_1") (pintype "passive"))
      (node (ref "U9") (pin "3") (pinfunction "SHUTDOWN_3") (pintype "bidirectional"))
    )
    (net (code "171") (name "OUT_L") (class "Default")
      (node (ref "C36") (pin "2") (pinfunction "2_2") (pintype "passive"))
      (node (ref "PHONE_OUT") (pin "4") (pinfunction "L_4") (pintype "bidirectional"))
      (node (ref "R25") (pin "2") (pinfunction "2_2") (pintype "passive"))
    )
    (net (code "172") (name "OUT_R") (class "Default")
      (node (ref "C39") (pin "2") (pinfunction "2_2") (pintype "passive"))
      (node (ref "PHONE_OUT") (pin "1") (pinfunction "R_1") (pintype "bidirectional"))
    )
    (net (code "173") (name "PA_EN") (class "Default")
      (node (ref "L12") (pin "2") (pinfunction "2_2") (pintype "passive"))
      (node (ref "R10") (pin "2") (pinfunction "2_2") (pintype "passive"))
      (node (ref "U2") (pin "5") (pinfunction "PAEN_5") (pintype "bidirectional"))
    )
    (net (code "174") (name "PHONE_L") (class "Default")
      (node (ref "PHONE_L") (pin "1") (pinfunction "P$1_1") (pintype "bidirectional"))
      (node (ref "U3") (pin "25") (pinfunction "HPL_25") (pintype "bidirectional"))
    )
    (net (code "175") (name "PHONE_R") (class "Default")
      (node (ref "PHONE_R") (pin "1") (pinfunction "P$1_1") (pintype "bidirectional"))
      (node (ref "U3") (pin "27") (pinfunction "HPR_27") (pintype "bidirectional"))
    )
    (net (code "176") (name "PHONE_SENSE") (class "Default")
      (node (ref "PHONE_SENSE") (pin "2") (pinfunction "P$2_2") (pintype "bidirectional"))
      (node (ref "U7") (pin "140") (pinfunction "PB14_140") (pintype "bidirectional"))
    )
    (net (code "177") (name "RED_BOT") (class "Default")
      (node (ref "RED_BOT") (pin "2") (pinfunction "P$2_2") (pintype "bidirectional"))
      (node (ref "U7") (pin "139") (pinfunction "PC28_139") (pintype "bidirectional"))
    )
    (net (code "178") (name "RED_TOP") (class "Default")
      (node (ref "RED_TOP") (pin "2") (pinfunction "P$2_2") (pintype "bidirectional"))
      (node (ref "U7") (pin "132") (pinfunction "PC21_132") (pintype "bidirectional"))
    )
    (net (code "179") (name "RESET_CC8531") (class "Default")
      (node (ref "CC8531_RESET") (pin "2") (pinfunction "P$2_2") (pintype "bidirectional"))
      (node (ref "U7") (pin "20") (pinfunction "PD7_20") (pintype "bidirectional"))
    )
    (net (code "180") (name "RESET_CODEC") (class "Default")
      (node (ref "CODEC_RESET") (pin "2") (pinfunction "P$2_2") (pintype "bidirectional"))
      (node (ref "U7") (pin "16") (pinfunction "PD3_16") (pintype "bidirectional"))
    )
    (net (code "181") (name "RF_N") (class "Default")
      (node (ref "U1") (pin "25") (pinfunction "RF_N_25") (pintype "bidirectional"))
      (node (ref "U2") (pin "2") (pinfunction "RF_N_2") (pintype "bidirectional"))
    )
    (net (code "182") (name "RF_P") (class "Default")
      (node (ref "U1") (pin "24") (pinfunction "RF_P_24") (pintype "bidirectional"))
      (node (ref "U2") (pin "4") (pinfunction "RF_P_4") (pintype "bidirectional"))
    )
    (net (code "183") (name "RX") (class "Default")
      (node (ref "U7") (pin "27") (pinfunction "PA8_27") (pintype "bidirectional"))
    )
    (net (code "184") (name "SCLK") (class "Default")
      (node (ref "AUX_SCLK") (pin "2") (pinfunction "P$2_2") (pintype "bidirectional"))
      (node (ref "CC8531_SCLK") (pin "2") (pinfunction "P$2_2") (pintype "bidirectional"))
      (node (ref "CODEC_SCLK") (pin "2") (pinfunction "P$2_2") (pintype "bidirectional"))
      (node (ref "SD_SCLK") (pin "1") (pinfunction "P$1_1") (pintype "bidirectional"))
      (node (ref "U7") (pin "110") (pinfunction "PA27_110") (pintype "bidirectional"))
    )
    (net (code "185") (name "S_BCLK") (class "Default")
      (node (ref "U7") (pin "90") (pinfunction "PB19_90") (pintype "bidirectional"))
    )
    (net (code "186") (name "S_WCLK") (class "Default")
      (node (ref "U7") (pin "88") (pinfunction "PB17_88") (pintype "bidirectional"))
    )
    (net (code "187") (name "TCK") (class "Default")
      (node (ref "JTAG") (pin "4") (pinfunction "4_4") (pintype "bidirectional"))
      (node (ref "R14") (pin "1") (pinfunction "1_1") (pintype "passive"))
      (node (ref "U7") (pin "28") (pinfunction "PB28_28") (pintype "bidirectional"))
    )
    (net (code "188") (name "TDI") (class "Default")
      (node (ref "JTAG") (pin "8") (pinfunction "8_8") (pintype "bidirectional"))
      (node (ref "R45") (pin "1") (pinfunction "1_1") (pintype "passive"))
      (node (ref "U7") (pin "29") (pinfunction "PB29_29") (pintype "bidirectional"))
    )
    (net (code "189") (name "TDO") (class "Default")
      (node (ref "JTAG") (pin "6") (pinfunction "6_6") (pintype "bidirectional"))
      (node (ref "U7") (pin "30") (pinfunction "PB30_30") (pintype "bidirectional"))
    )
    (net (code "190") (name "TMS") (class "Default")
      (node (ref "JTAG") (pin "2") (pinfunction "2_2") (pintype "bidirectional"))
      (node (ref "R11") (pin "1") (pinfunction "1_1") (pintype "passive"))
      (node (ref "U7") (pin "31") (pinfunction "PB31_31") (pintype "bidirectional"))
    )
    (net (code "191") (name "TX") (class "Default")
      (node (ref "U7") (pin "2") (pinfunction "PA9_2") (pintype "bidirectional"))
    )
    (net (code "192") (name "USBOTGID") (class "Default")
      (node (ref "U7") (pin "129") (pinfunction "PB11_129") (pintype "bidirectional"))
      (node (ref "USB2") (pin "4") (pinfunction "ID_4") (pintype "bidirectional"))
    )
    (net (code "193") (name "USB_SENSE") (class "Default")
      (node (ref "U7") (pin "19") (pinfunction "PD6_19") (pintype "bidirectional"))
      (node (ref "USB_SENSE") (pin "2") (pinfunction "P$2_2") (pintype "bidirectional"))
    )
    (net (code "194") (name "WCLK") (class "Default")
      (node (ref "CC8531_WCLK") (pin "2") (pinfunction "P$2_2") (pintype "bidirectional"))
      (node (ref "U3") (pin "3") (pinfunction "WCLK_3") (pintype "bidirectional"))
      (node (ref "WCLK") (pin "1") (pinfunction "P$1_1") (pintype "bidirectional"))
    )
    (net (code "195") (name "X_BCLK") (class "Default")
      (node (ref "CC8531_BCLK") (pin "1") (pinfunction "P$1_1") (pintype "bidirectional"))
      (node (ref "L6") (pin "1") (pinfunction "1_1") (pintype "passive"))
    )
    (net (code "196") (name "X_CS_CC8531") (class "Default")
      (node (ref "CC8531_CS") (pin "1") (pinfunction "P$1_1") (pintype "bidirectional"))
      (node (ref "CC_DEBUG") (pin "5") (pinfunction "5_5") (pintype "bidirectional"))
      (node (ref "U1") (pin "3") (pinfunction "CSN_3") (pintype "bidirectional"))
    )
    (net (code "197") (name "X_DIN") (class "Default")
      (node (ref "CC8531_DIN") (pin "1") (pinfunction "P$1_1") (pintype "bidirectional"))
      (node (ref "L13") (pin "1") (pinfunction "1_1") (pintype "passive"))
    )
    (net (code "198") (name "X_DOUT") (class "Default")
      (node (ref "CC8531_DOUT") (pin "1") (pinfunction "P$1_1") (pintype "bidirectional"))
      (node (ref "L11") (pin "1") (pinfunction "1_1") (pintype "passive"))
    )
    (net (code "199") (name "X_MCLK") (class "Default")
      (node (ref "CC8531_MCLK") (pin "1") (pinfunction "P$1_1") (pintype "bidirectional"))
      (node (ref "L5") (pin "1") (pinfunction "1_1") (pintype "passive"))
    )
    (net (code "200") (name "X_MISO") (class "Default")
      (node (ref "CC8531_MISO") (pin "1") (pinfunction "P$1_1") (pintype "bidirectional"))
      (node (ref "CC_DEBUG") (pin "10") (pinfunction "10_10") (pintype "bidirectional"))
      (node (ref "U1") (pin "6") (pinfunction "MISO_6") (pintype "bidirectional"))
    )
    (net (code "201") (name "X_MOSI") (class "Default")
      (node (ref "CC8531_MOSI") (pin "1") (pinfunction "P$1_1") (pintype "bidirectional"))
      (node (ref "CC_DEBUG") (pin "8") (pinfunction "8_8") (pintype "bidirectional"))
      (node (ref "U1") (pin "5") (pinfunction "MOSI_5") (pintype "bidirectional"))
    )
    (net (code "202") (name "X_RESET_CC8531") (class "Default")
      (node (ref "CC8531_RESET") (pin "1") (pinfunction "P$1_1") (pintype "bidirectional"))
      (node (ref "CC_DEBUG") (pin "7") (pinfunction "7_7") (pintype "bidirectional"))
      (node (ref "L4") (pin "2") (pinfunction "2_2") (pintype "passive"))
    )
    (net (code "203") (name "X_SCLK") (class "Default")
      (node (ref "CC8531_SCLK") (pin "1") (pinfunction "P$1_1") (pintype "bidirectional"))
      (node (ref "CC_DEBUG") (pin "6") (pinfunction "6_6") (pintype "bidirectional"))
      (node (ref "U1") (pin "4") (pinfunction "SCLK_4") (pintype "bidirectional"))
    )
    (net (code "204") (name "X_USB_SENSE") (class "Default")
      (node (ref "R7") (pin "1") (pinfunction "1_1") (pintype "passive"))
      (node (ref "U1") (pin "19") (pinfunction "AD2/GIO9_19") (pintype "bidirectional"))
      (node (ref "USB_SENSE") (pin "1") (pinfunction "P$1_1") (pintype "bidirectional"))
    )
    (net (code "205") (name "X_WCLK") (class "Default")
      (node (ref "CC8531_WCLK") (pin "1") (pinfunction "P$1_1") (pintype "bidirectional"))
      (node (ref "L9") (pin "1") (pinfunction "1_1") (pintype "passive"))
    )
    (net (code "206") (name "unconnected-(CC_DEBUG-Pad3)") (class "Default")
      (node (ref "CC_DEBUG") (pin "3") (pinfunction "3_3") (pintype "bidirectional"))
    )
    (net (code "207") (name "unconnected-(CC_DEBUG-Pad4)") (class "Default")
      (node (ref "CC_DEBUG") (pin "4") (pinfunction "4_4") (pintype "bidirectional"))
    )
    (net (code "208") (name "unconnected-(ERASE-Pad2)") (class "Default")
      (node (ref "ERASE") (pin "2") (pinfunction "2_2") (pintype "bidirectional"))
    )
    (net (code "209") (name "unconnected-(ERASE-Pad4)") (class "Default")
      (node (ref "ERASE") (pin "4") (pinfunction "4_4") (pintype "bidirectional"))
    )
    (net (code "210") (name "unconnected-(JTAG-Pad7)") (class "Default")
      (node (ref "JTAG") (pin "7") (pinfunction "7_7") (pintype "bidirectional"))
    )
    (net (code "211") (name "unconnected-(LINE_IN-R_SW-Pad2)") (class "Default")
      (node (ref "LINE_IN") (pin "2") (pinfunction "R_SW_2") (pintype "bidirectional"))
    )
    (net (code "212") (name "unconnected-(PHONE_OUT-R_SW-Pad2)") (class "Default")
      (node (ref "PHONE_OUT") (pin "2") (pinfunction "R_SW_2") (pintype "bidirectional"))
    )
    (net (code "213") (name "unconnected-(RESET-Pad2)") (class "Default")
      (node (ref "RESET") (pin "2") (pinfunction "2_2") (pintype "bidirectional"))
    )
    (net (code "214") (name "unconnected-(RESET-Pad4)") (class "Default")
      (node (ref "RESET") (pin "4") (pinfunction "4_4") (pintype "bidirectional"))
    )
    (net (code "215") (name "unconnected-(U1-SCL{slash}GIO10-Pad32)") (class "Default")
      (node (ref "U1") (pin "32") (pinfunction "SCL/GIO10_32") (pintype "bidirectional"))
    )
    (net (code "216") (name "unconnected-(U1-SDA{slash}GIO11-Pad33)") (class "Default")
      (node (ref "U1") (pin "33") (pinfunction "SDA/GIO11_33") (pintype "bidirectional"))
    )
    (net (code "217") (name "unconnected-(U2-RXTX-Pad3)") (class "Default")
      (node (ref "U2") (pin "3") (pinfunction "RXTX_3") (pintype "bidirectional"))
    )
    (net (code "218") (name "unconnected-(U3-GPIO{slash}MFP5-Pad32)") (class "Default")
      (node (ref "U3") (pin "32") (pinfunction "GPIO/MFP5_32") (pintype "bidirectional"))
    )
    (net (code "219") (name "unconnected-(U3-IN2_L-Pad15)") (class "Default")
      (node (ref "U3") (pin "15") (pinfunction "IN2_L_15") (pintype "bidirectional"))
    )
    (net (code "220") (name "unconnected-(U3-IN2_R-Pad16)") (class "Default")
      (node (ref "U3") (pin "16") (pinfunction "IN2_R_16") (pintype "bidirectional"))
    )
    (net (code "221") (name "unconnected-(U3-IN3_L-Pad20)") (class "Default")
      (node (ref "U3") (pin "20") (pinfunction "IN3_L_20") (pintype "bidirectional"))
    )
    (net (code "222") (name "unconnected-(U3-IN3_R-Pad21)") (class "Default")
      (node (ref "U3") (pin "21") (pinfunction "IN3_R_21") (pintype "bidirectional"))
    )
    (net (code "223") (name "unconnected-(U3-MICBIAS-Pad19)") (class "Default")
      (node (ref "U3") (pin "19") (pinfunction "MICBIAS_19") (pintype "bidirectional"))
    )
    (net (code "224") (name "unconnected-(U7A-PA0-Pad23)") (class "Default")
      (node (ref "U7") (pin "23") (pinfunction "PA0_23") (pintype "bidirectional"))
    )
    (net (code "225") (name "unconnected-(U7A-PA1-Pad24)") (class "Default")
      (node (ref "U7") (pin "24") (pinfunction "PA1_24") (pintype "bidirectional"))
    )
    (net (code "226") (name "unconnected-(U7A-PA3-Pad84)") (class "Default")
      (node (ref "U7") (pin "84") (pinfunction "PA3_84") (pintype "bidirectional"))
    )
    (net (code "227") (name "unconnected-(U7A-PA4-Pad83)") (class "Default")
      (node (ref "U7") (pin "83") (pinfunction "PA4_83") (pintype "bidirectional"))
    )
    (net (code "228") (name "unconnected-(U7A-PA5-Pad25)") (class "Default")
      (node (ref "U7") (pin "25") (pinfunction "PA5_25") (pintype "bidirectional"))
    )
    (net (code "229") (name "unconnected-(U7A-PA6-Pad82)") (class "Default")
      (node (ref "U7") (pin "82") (pinfunction "PA6_82") (pintype "bidirectional"))
    )
    (net (code "230") (name "unconnected-(U7A-PA10-Pad3)") (class "Default")
      (node (ref "U7") (pin "3") (pinfunction "PA10_3") (pintype "bidirectional"))
    )
    (net (code "231") (name "unconnected-(U7A-PA11-Pad4)") (class "Default")
      (node (ref "U7") (pin "4") (pinfunction "PA11_4") (pintype "bidirectional"))
    )
    (net (code "232") (name "unconnected-(U7A-PA12-Pad5)") (class "Default")
      (node (ref "U7") (pin "5") (pinfunction "PA12_5") (pintype "bidirectional"))
    )
    (net (code "233") (name "unconnected-(U7A-PA13-Pad6)") (class "Default")
      (node (ref "U7") (pin "6") (pinfunction "PA13_6") (pintype "bidirectional"))
    )
    (net (code "234") (name "unconnected-(U7A-PA17-Pad9)") (class "Default")
      (node (ref "U7") (pin "9") (pinfunction "PA17_9") (pintype "bidirectional"))
    )
    (net (code "235") (name "unconnected-(U7A-PA18-Pad70)") (class "Default")
      (node (ref "U7") (pin "70") (pinfunction "PA18_70") (pintype "bidirectional"))
    )
    (net (code "236") (name "unconnected-(U7A-PA21-Pad107)") (class "Default")
      (node (ref "U7") (pin "107") (pinfunction "PA21_107") (pintype "bidirectional"))
    )
    (net (code "237") (name "unconnected-(U7A-PA22-Pad81)") (class "Default")
      (node (ref "U7") (pin "81") (pinfunction "PA22_81") (pintype "bidirectional"))
    )
    (net (code "238") (name "unconnected-(U7A-PA23-Pad80)") (class "Default")
      (node (ref "U7") (pin "80") (pinfunction "PA23_80") (pintype "bidirectional"))
    )
    (net (code "239") (name "unconnected-(U7A-PA24-Pad79)") (class "Default")
      (node (ref "U7") (pin "79") (pinfunction "PA24_79") (pintype "bidirectional"))
    )
    (net (code "240") (name "unconnected-(U7A-PA28-Pad111)") (class "Default")
      (node (ref "U7") (pin "111") (pinfunction "PA28_111") (pintype "bidirectional"))
    )
    (net (code "241") (name "unconnected-(U7A-PA29-Pad112)") (class "Default")
      (node (ref "U7") (pin "112") (pinfunction "PA29_112") (pintype "bidirectional"))
    )
    (net (code "242") (name "unconnected-(U7B-PB0-Pad113)") (class "Default")
      (node (ref "U7") (pin "113") (pinfunction "PB0_113") (pintype "bidirectional"))
    )
    (net (code "243") (name "unconnected-(U7B-PB1-Pad114)") (class "Default")
      (node (ref "U7") (pin "114") (pinfunction "PB1_114") (pintype "bidirectional"))
    )
    (net (code "244") (name "unconnected-(U7B-PB2-Pad115)") (class "Default")
      (node (ref "U7") (pin "115") (pinfunction "PB2_115") (pintype "bidirectional"))
    )
    (net (code "245") (name "unconnected-(U7B-PB3-Pad118)") (class "Default")
      (node (ref "U7") (pin "118") (pinfunction "PB3_118") (pintype "bidirectional"))
    )
    (net (code "246") (name "unconnected-(U7B-PB4-Pad119)") (class "Default")
      (node (ref "U7") (pin "119") (pinfunction "PB4_119") (pintype "bidirectional"))
    )
    (net (code "247") (name "unconnected-(U7B-PB5-Pad120)") (class "Default")
      (node (ref "U7") (pin "120") (pinfunction "PB5_120") (pintype "bidirectional"))
    )
    (net (code "248") (name "unconnected-(U7B-PB6-Pad121)") (class "Default")
      (node (ref "U7") (pin "121") (pinfunction "PB6_121") (pintype "bidirectional"))
    )
    (net (code "249") (name "unconnected-(U7B-PB7-Pad122)") (class "Default")
      (node (ref "U7") (pin "122") (pinfunction "PB7_122") (pintype "bidirectional"))
    )
    (net (code "250") (name "unconnected-(U7B-PB8-Pad123)") (class "Default")
      (node (ref "U7") (pin "123") (pinfunction "PB8_123") (pintype "bidirectional"))
    )
    (net (code "251") (name "unconnected-(U7B-PB9-Pad127)") (class "Default")
      (node (ref "U7") (pin "127") (pinfunction "PB9_127") (pintype "bidirectional"))
    )
    (net (code "252") (name "unconnected-(U7B-PB10-Pad128)") (class "Default")
      (node (ref "U7") (pin "128") (pinfunction "PB10_128") (pintype "bidirectional"))
    )
    (net (code "253") (name "unconnected-(U7B-PB12-Pad86)") (class "Default")
      (node (ref "U7") (pin "86") (pinfunction "PB12_86") (pintype "bidirectional"))
    )
    (net (code "254") (name "unconnected-(U7B-PB13-Pad87)") (class "Default")
      (node (ref "U7") (pin "87") (pinfunction "PB13_87") (pintype "bidirectional"))
    )
    (net (code "255") (name "unconnected-(U7B-PB15-Pad76)") (class "Default")
      (node (ref "U7") (pin "76") (pinfunction "PB15_76") (pintype "bidirectional"))
    )
    (net (code "256") (name "unconnected-(U7B-PB16-Pad77)") (class "Default")
      (node (ref "U7") (pin "77") (pinfunction "PB16_77") (pintype "bidirectional"))
    )
    (net (code "257") (name "unconnected-(U7B-PB20-Pad91)") (class "Default")
      (node (ref "U7") (pin "91") (pinfunction "PB20_91") (pintype "bidirectional"))
    )
    (net (code "258") (name "unconnected-(U7B-PB21-Pad92)") (class "Default")
      (node (ref "U7") (pin "92") (pinfunction "PB21_92") (pintype "bidirectional"))
    )
    (net (code "259") (name "unconnected-(U7B-PB22-Pad141)") (class "Default")
      (node (ref "U7") (pin "141") (pinfunction "PB22_141") (pintype "bidirectional"))
    )
    (net (code "260") (name "unconnected-(U7B-PB23-Pad142)") (class "Default")
      (node (ref "U7") (pin "142") (pinfunction "PB23_142") (pintype "bidirectional"))
    )
    (net (code "261") (name "unconnected-(U7B-PB24-Pad143)") (class "Default")
      (node (ref "U7") (pin "143") (pinfunction "PB24_143") (pintype "bidirectional"))
    )
    (net (code "262") (name "unconnected-(U7B-PB25-Pad144)") (class "Default")
      (node (ref "U7") (pin "144") (pinfunction "PB25_144") (pintype "bidirectional"))
    )
    (net (code "263") (name "unconnected-(U7B-PB26-Pad1)") (class "Default")
      (node (ref "U7") (pin "1") (pinfunction "PB26_1") (pintype "bidirectional"))
    )
    (net (code "264") (name "unconnected-(U7C-PC1-Pad55)") (class "Default")
      (node (ref "U7") (pin "55") (pinfunction "PC1_55") (pintype "bidirectional"))
    )
    (net (code "265") (name "unconnected-(U7C-PC2-Pad59)") (class "Default")
      (node (ref "U7") (pin "59") (pinfunction "PC2_59") (pintype "bidirectional"))
    )
    (net (code "266") (name "unconnected-(U7C-PC3-Pad60)") (class "Default")
      (node (ref "U7") (pin "60") (pinfunction "PC3_60") (pintype "bidirectional"))
    )
    (net (code "267") (name "unconnected-(U7C-PC4-Pad116)") (class "Default")
      (node (ref "U7") (pin "116") (pinfunction "PC4_116") (pintype "bidirectional"))
    )
    (net (code "268") (name "unconnected-(U7C-PC5-Pad63)") (class "Default")
      (node (ref "U7") (pin "63") (pinfunction "PC5_63") (pintype "bidirectional"))
    )
    (net (code "269") (name "unconnected-(U7C-PC6-Pad64)") (class "Default")
      (node (ref "U7") (pin "64") (pinfunction "PC6_64") (pintype "bidirectional"))
    )
    (net (code "270") (name "unconnected-(U7C-PC7-Pad65)") (class "Default")
      (node (ref "U7") (pin "65") (pinfunction "PC7_65") (pintype "bidirectional"))
    )
    (net (code "271") (name "unconnected-(U7C-PC10-Pad117)") (class "Default")
      (node (ref "U7") (pin "117") (pinfunction "PC10_117") (pintype "bidirectional"))
    )
    (net (code "272") (name "unconnected-(U7C-PC11-Pad93)") (class "Default")
      (node (ref "U7") (pin "93") (pinfunction "PC11_93") (pintype "bidirectional"))
    )
    (net (code "273") (name "unconnected-(U7C-PC12-Pad94)") (class "Default")
      (node (ref "U7") (pin "94") (pinfunction "PC12_94") (pintype "bidirectional"))
    )
    (net (code "274") (name "unconnected-(U7C-PC13-Pad95)") (class "Default")
      (node (ref "U7") (pin "95") (pinfunction "PC13_95") (pintype "bidirectional"))
    )
    (net (code "275") (name "unconnected-(U7C-PC14-Pad96)") (class "Default")
      (node (ref "U7") (pin "96") (pinfunction "PC14_96") (pintype "bidirectional"))
    )
    (net (code "276") (name "unconnected-(U7C-PC15-Pad97)") (class "Default")
      (node (ref "U7") (pin "97") (pinfunction "PC15_97") (pintype "bidirectional"))
    )
    (net (code "277") (name "unconnected-(U7C-PC16-Pad98)") (class "Default")
      (node (ref "U7") (pin "98") (pinfunction "PC16_98") (pintype "bidirectional"))
    )
    (net (code "278") (name "unconnected-(U7C-PC17-Pad99)") (class "Default")
      (node (ref "U7") (pin "99") (pinfunction "PC17_99") (pintype "bidirectional"))
    )
    (net (code "279") (name "unconnected-(U7C-PC18-Pad100)") (class "Default")
      (node (ref "U7") (pin "100") (pinfunction "PC18_100") (pintype "bidirectional"))
    )
    (net (code "280") (name "unconnected-(U7C-PC20-Pad131)") (class "Default")
      (node (ref "U7") (pin "131") (pinfunction "PC20_131") (pintype "bidirectional"))
    )
    (net (code "281") (name "unconnected-(U7C-PC26-Pad137)") (class "Default")
      (node (ref "U7") (pin "137") (pinfunction "PC26_137") (pintype "bidirectional"))
    )
    (net (code "282") (name "unconnected-(U7C-PC27-Pad138)") (class "Default")
      (node (ref "U7") (pin "138") (pinfunction "PC27_138") (pintype "bidirectional"))
    )
    (net (code "283") (name "unconnected-(U7C-PC29-Pad102)") (class "Default")
      (node (ref "U7") (pin "102") (pinfunction "PC29_102") (pintype "bidirectional"))
    )
    (net (code "284") (name "unconnected-(U7C-PC30-Pad103)") (class "Default")
      (node (ref "U7") (pin "103") (pinfunction "PC30_103") (pintype "bidirectional"))
    )
    (net (code "285") (name "unconnected-(U7D-PD0-Pad13)") (class "Default")
      (node (ref "U7") (pin "13") (pinfunction "PD0_13") (pintype "bidirectional"))
    )
    (net (code "286") (name "unconnected-(U7D-PD1-Pad14)") (class "Default")
      (node (ref "U7") (pin "14") (pinfunction "PD1_14") (pintype "bidirectional"))
    )
    (net (code "287") (name "unconnected-(U7D-PD4-Pad17)") (class "Default")
      (node (ref "U7") (pin "17") (pinfunction "PD4_17") (pintype "bidirectional"))
    )
    (net (code "288") (name "unconnected-(U7D-PD5-Pad18)") (class "Default")
      (node (ref "U7") (pin "18") (pinfunction "PD5_18") (pintype "bidirectional"))
    )
    (net (code "289") (name "unconnected-(U7F-NRST-Pad69)") (class "Default")
      (node (ref "U7") (pin "69") (pinfunction "NRST_69") (pintype "bidirectional"))
    )
    (net (code "290") (name "unconnected-(U7F-SHDN-Pad50)") (class "Default")
      (node (ref "U7") (pin "50") (pinfunction "SHDN_50") (pintype "bidirectional"))
    )
    (net (code "291") (name "unconnected-(U7F-TST-Pad51)") (class "Default")
      (node (ref "U7") (pin "51") (pinfunction "TST_51") (pintype "bidirectional"))
    )
    (net (code "292") (name "unconnected-(U7F-XIN32-Pad48)") (class "Default")
      (node (ref "U7") (pin "48") (pinfunction "XIN32_48") (pintype "bidirectional"))
    )
    (net (code "293") (name "unconnected-(U7F-XOUT32-Pad49)") (class "Default")
      (node (ref "U7") (pin "49") (pinfunction "XOUT32_49") (pintype "bidirectional"))
    )
    (net (code "294") (name "unconnected-(U8-SNS0-Pad32)") (class "Default")
      (node (ref "U8") (pin "32") (pinfunction "SNS0_32") (pintype "bidirectional"))
    )
    (net (code "295") (name "unconnected-(U8-SNS0K-Pad1)") (class "Default")
      (node (ref "U8") (pin "1") (pinfunction "SNS0K_1") (pintype "bidirectional"))
    )
    (net (code "296") (name "unconnected-(U8-SNS1-Pad2)") (class "Default")
      (node (ref "U8") (pin "2") (pinfunction "SNS1_2") (pintype "bidirectional"))
    )
    (net (code "297") (name "unconnected-(U8-SNS1K-Pad3)") (class "Default")
      (node (ref "U8") (pin "3") (pinfunction "SNS1K_3") (pintype "bidirectional"))
    )
    (net (code "298") (name "unconnected-(U8-SNS2-Pad7)") (class "Default")
      (node (ref "U8") (pin "7") (pinfunction "SNS2_7") (pintype "bidirectional"))
    )
    (net (code "299") (name "unconnected-(U8-SNS2K-Pad6)") (class "Default")
      (node (ref "U8") (pin "6") (pinfunction "SNS2K_6") (pintype "bidirectional"))
    )
    (net (code "300") (name "unconnected-(USB1-ID-Pad4)") (class "Default")
      (node (ref "USB1") (pin "4") (pinfunction "ID_4") (pintype "bidirectional"))
    )
  )
)
